# 2_10decoder.net
KiCad netlist of a schematic drawn in EAGLE
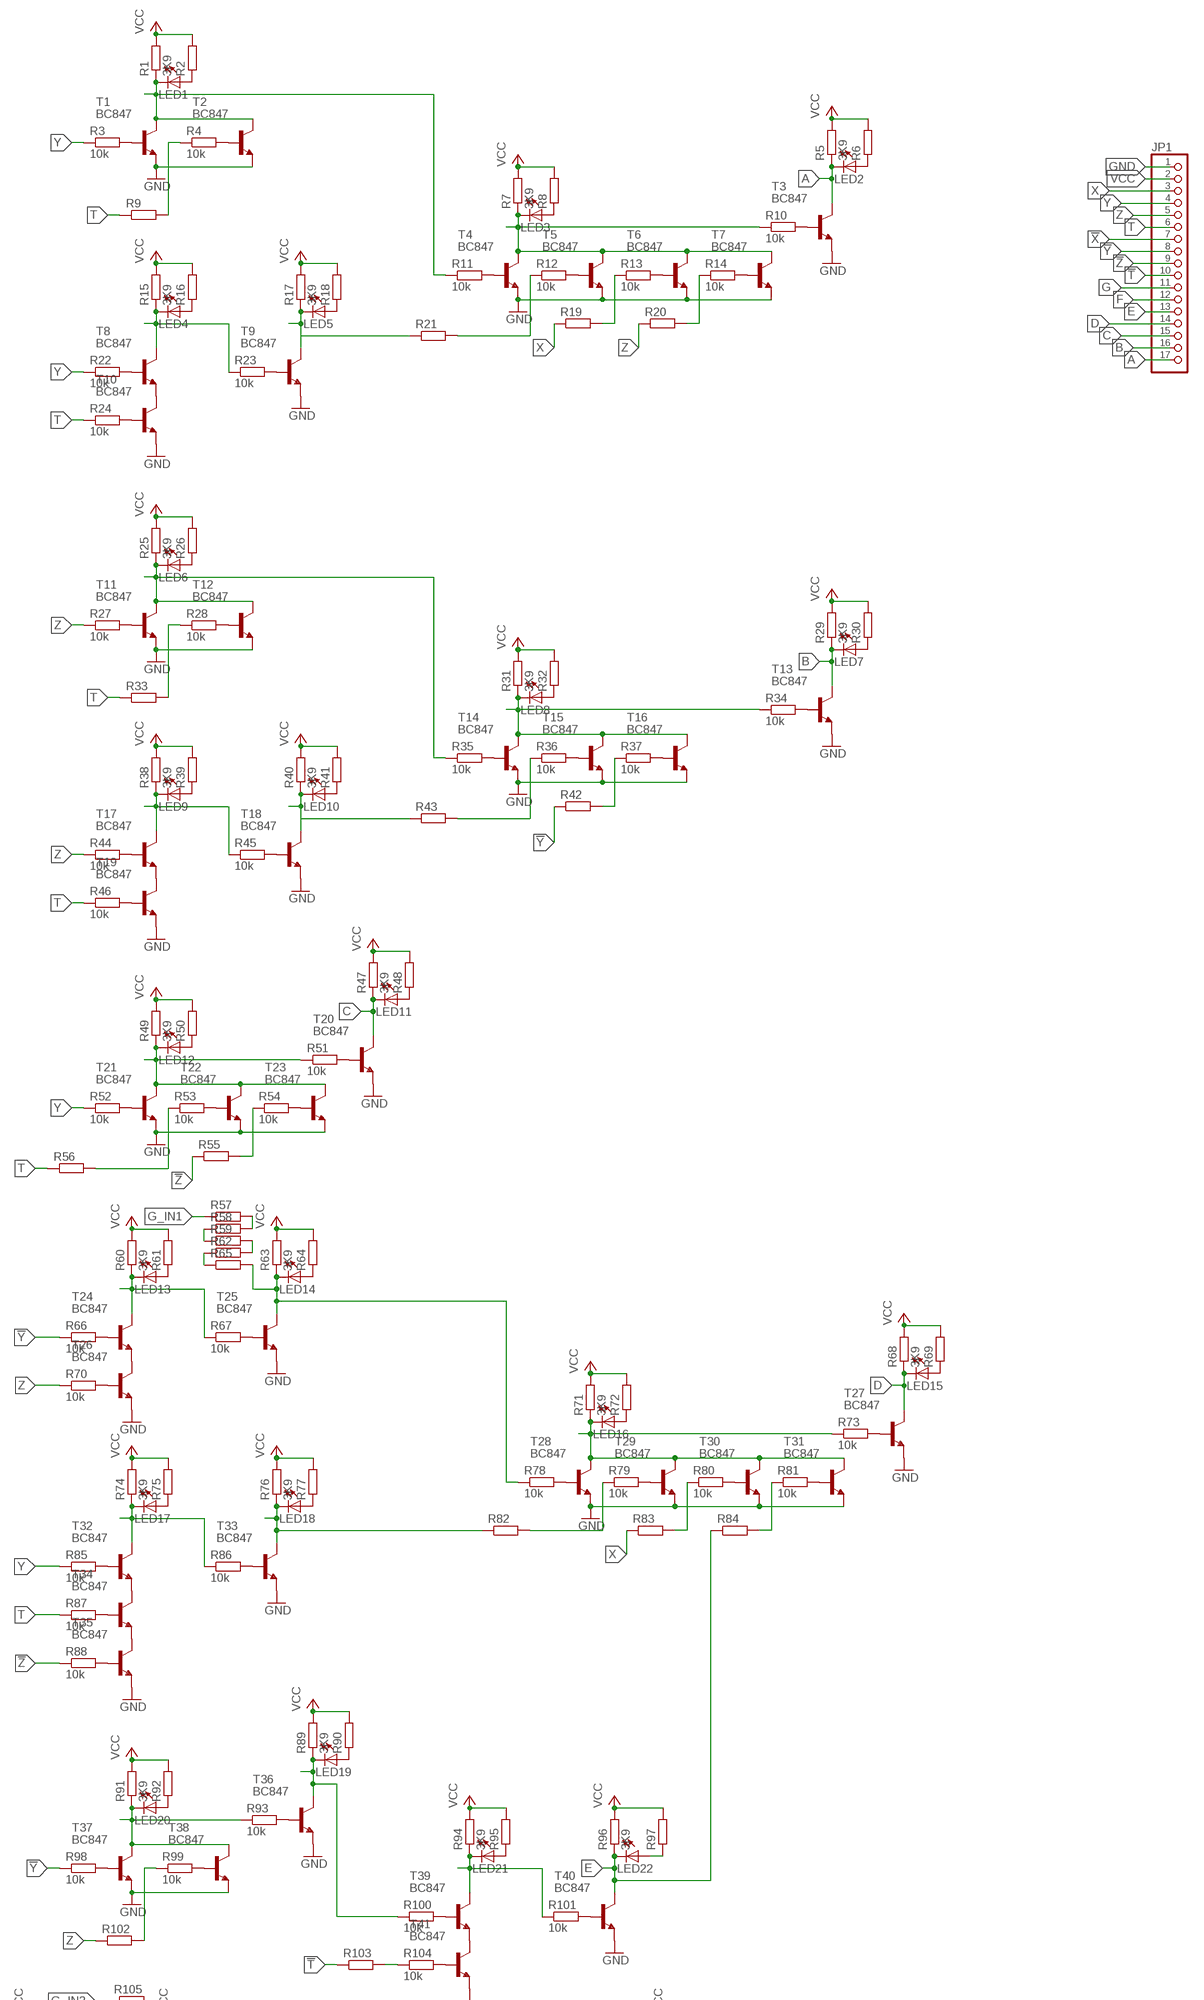
[diagram p0: schematic, sheet 1, part 1 of 2]
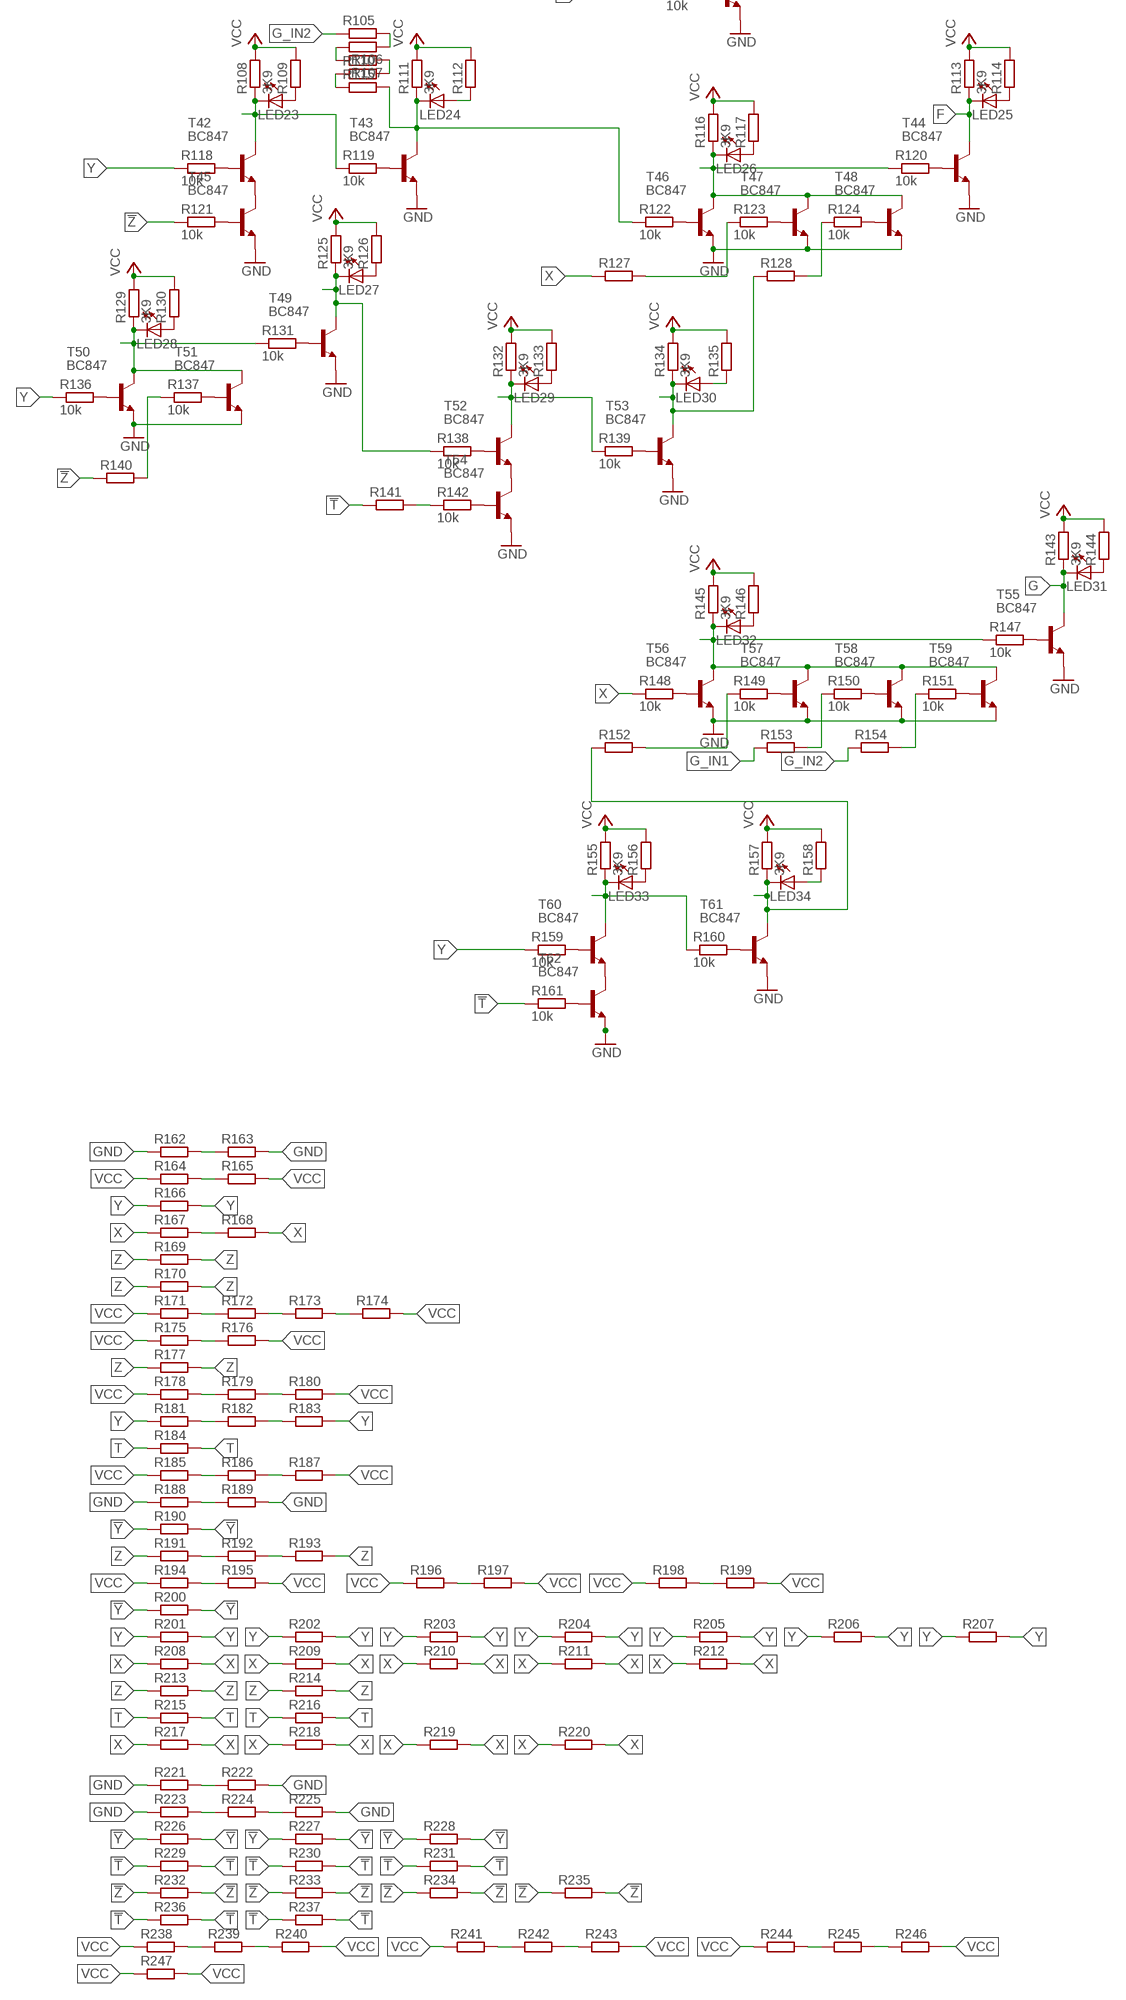
[diagram p1: schematic, sheet 1, part 2 of 2]

(export (version "E")
  (design (tool "Eeschema 10.0.6"))
  (components
    (comp (ref "JP1")
      (value "PINHD-1X17_2.54-SMD-90°")
      (footprint "eagle-import:1X17SMD_90")
      (libsource (lib "eagle-import") (part "PINHD-1X17_2.54-SMD-90°"))
    )
    (comp (ref "LED1")
      (value "LEDCHIP-LED0805")
      (footprint "eagle-import:CHIP-LED0805")
      (libsource (lib "eagle-import") (part "LEDCHIP-LED0805"))
    )
    (comp (ref "LED2")
      (value "LEDCHIP-LED0805")
      (footprint "eagle-import:CHIP-LED0805")
      (libsource (lib "eagle-import") (part "LEDCHIP-LED0805"))
    )
    (comp (ref "LED3")
      (value "LEDCHIP-LED0805")
      (footprint "eagle-import:CHIP-LED0805")
      (libsource (lib "eagle-import") (part "LEDCHIP-LED0805"))
    )
    (comp (ref "LED4")
      (value "LEDCHIP-LED0805")
      (footprint "eagle-import:CHIP-LED0805")
      (libsource (lib "eagle-import") (part "LEDCHIP-LED0805"))
    )
    (comp (ref "LED5")
      (value "LEDCHIP-LED0805")
      (footprint "eagle-import:CHIP-LED0805")
      (libsource (lib "eagle-import") (part "LEDCHIP-LED0805"))
    )
    (comp (ref "LED6")
      (value "LEDCHIP-LED0805")
      (footprint "eagle-import:CHIP-LED0805")
      (libsource (lib "eagle-import") (part "LEDCHIP-LED0805"))
    )
    (comp (ref "LED7")
      (value "LEDCHIP-LED0805")
      (footprint "eagle-import:CHIP-LED0805")
      (libsource (lib "eagle-import") (part "LEDCHIP-LED0805"))
    )
    (comp (ref "LED8")
      (value "LEDCHIP-LED0805")
      (footprint "eagle-import:CHIP-LED0805")
      (libsource (lib "eagle-import") (part "LEDCHIP-LED0805"))
    )
    (comp (ref "LED9")
      (value "LEDCHIP-LED0805")
      (footprint "eagle-import:CHIP-LED0805")
      (libsource (lib "eagle-import") (part "LEDCHIP-LED0805"))
    )
    (comp (ref "LED10")
      (value "LEDCHIP-LED0805")
      (footprint "eagle-import:CHIP-LED0805")
      (libsource (lib "eagle-import") (part "LEDCHIP-LED0805"))
    )
    (comp (ref "LED11")
      (value "LEDCHIP-LED0805")
      (footprint "eagle-import:CHIP-LED0805")
      (libsource (lib "eagle-import") (part "LEDCHIP-LED0805"))
    )
    (comp (ref "LED12")
      (value "LEDCHIP-LED0805")
      (footprint "eagle-import:CHIP-LED0805")
      (libsource (lib "eagle-import") (part "LEDCHIP-LED0805"))
    )
    (comp (ref "LED13")
      (value "LEDCHIP-LED0805")
      (footprint "eagle-import:CHIP-LED0805")
      (libsource (lib "eagle-import") (part "LEDCHIP-LED0805"))
    )
    (comp (ref "LED14")
      (value "LEDCHIP-LED0805")
      (footprint "eagle-import:CHIP-LED0805")
      (libsource (lib "eagle-import") (part "LEDCHIP-LED0805"))
    )
    (comp (ref "LED15")
      (value "LEDCHIP-LED0805")
      (footprint "eagle-import:CHIP-LED0805")
      (libsource (lib "eagle-import") (part "LEDCHIP-LED0805"))
    )
    (comp (ref "LED16")
      (value "LEDCHIP-LED0805")
      (footprint "eagle-import:CHIP-LED0805")
      (libsource (lib "eagle-import") (part "LEDCHIP-LED0805"))
    )
    (comp (ref "LED17")
      (value "LEDCHIP-LED0805")
      (footprint "eagle-import:CHIP-LED0805")
      (libsource (lib "eagle-import") (part "LEDCHIP-LED0805"))
    )
    (comp (ref "LED18")
      (value "LEDCHIP-LED0805")
      (footprint "eagle-import:CHIP-LED0805")
      (libsource (lib "eagle-import") (part "LEDCHIP-LED0805"))
    )
    (comp (ref "LED19")
      (value "LEDCHIP-LED0805")
      (footprint "eagle-import:CHIP-LED0805")
      (libsource (lib "eagle-import") (part "LEDCHIP-LED0805"))
    )
    (comp (ref "LED20")
      (value "LEDCHIP-LED0805")
      (footprint "eagle-import:CHIP-LED0805")
      (libsource (lib "eagle-import") (part "LEDCHIP-LED0805"))
    )
    (comp (ref "LED21")
      (value "LEDCHIP-LED0805")
      (footprint "eagle-import:CHIP-LED0805")
      (libsource (lib "eagle-import") (part "LEDCHIP-LED0805"))
    )
    (comp (ref "LED22")
      (value "LEDCHIP-LED0805")
      (footprint "eagle-import:CHIP-LED0805")
      (libsource (lib "eagle-import") (part "LEDCHIP-LED0805"))
    )
    (comp (ref "LED23")
      (value "LEDCHIP-LED0805")
      (footprint "eagle-import:CHIP-LED0805")
      (libsource (lib "eagle-import") (part "LEDCHIP-LED0805"))
    )
    (comp (ref "LED24")
      (value "LEDCHIP-LED0805")
      (footprint "eagle-import:CHIP-LED0805")
      (libsource (lib "eagle-import") (part "LEDCHIP-LED0805"))
    )
    (comp (ref "LED25")
      (value "LEDCHIP-LED0805")
      (footprint "eagle-import:CHIP-LED0805")
      (libsource (lib "eagle-import") (part "LEDCHIP-LED0805"))
    )
    (comp (ref "LED26")
      (value "LEDCHIP-LED0805")
      (footprint "eagle-import:CHIP-LED0805")
      (libsource (lib "eagle-import") (part "LEDCHIP-LED0805"))
    )
    (comp (ref "LED27")
      (value "LEDCHIP-LED0805")
      (footprint "eagle-import:CHIP-LED0805")
      (libsource (lib "eagle-import") (part "LEDCHIP-LED0805"))
    )
    (comp (ref "LED28")
      (value "LEDCHIP-LED0805")
      (footprint "eagle-import:CHIP-LED0805")
      (libsource (lib "eagle-import") (part "LEDCHIP-LED0805"))
    )
    (comp (ref "LED29")
      (value "LEDCHIP-LED0805")
      (footprint "eagle-import:CHIP-LED0805")
      (libsource (lib "eagle-import") (part "LEDCHIP-LED0805"))
    )
    (comp (ref "LED30")
      (value "LEDCHIP-LED0805")
      (footprint "eagle-import:CHIP-LED0805")
      (libsource (lib "eagle-import") (part "LEDCHIP-LED0805"))
    )
    (comp (ref "LED31")
      (value "LEDCHIP-LED0805")
      (footprint "eagle-import:CHIP-LED0805")
      (libsource (lib "eagle-import") (part "LEDCHIP-LED0805"))
    )
    (comp (ref "LED32")
      (value "LEDCHIP-LED0805")
      (footprint "eagle-import:CHIP-LED0805")
      (libsource (lib "eagle-import") (part "LEDCHIP-LED0805"))
    )
    (comp (ref "LED33")
      (value "LEDCHIP-LED0805")
      (footprint "eagle-import:CHIP-LED0805")
      (libsource (lib "eagle-import") (part "LEDCHIP-LED0805"))
    )
    (comp (ref "LED34")
      (value "LEDCHIP-LED0805")
      (footprint "eagle-import:CHIP-LED0805")
      (libsource (lib "eagle-import") (part "LEDCHIP-LED0805"))
    )
    (comp (ref "R1")
      (value "3K9")
      (footprint "eagle-import:M0805")
      (libsource (lib "eagle-import") (part "resistor_348_R-EU_M0805"))
    )
    (comp (ref "R2")
      (value "R-EU_M0805")
      (footprint "eagle-import:M0805")
      (libsource (lib "eagle-import") (part "resistor_348_R-EU_M0805"))
    )
    (comp (ref "R3")
      (value "10k")
      (footprint "eagle-import:M0805")
      (libsource (lib "eagle-import") (part "resistor_348_R-EU_M0805"))
    )
    (comp (ref "R4")
      (value "10k")
      (footprint "eagle-import:M0805")
      (libsource (lib "eagle-import") (part "resistor_348_R-EU_M0805"))
    )
    (comp (ref "R5")
      (value "3K9")
      (footprint "eagle-import:M0805")
      (libsource (lib "eagle-import") (part "resistor_348_R-EU_M0805"))
    )
    (comp (ref "R6")
      (value "R-EU_M0805")
      (footprint "eagle-import:M0805")
      (libsource (lib "eagle-import") (part "resistor_348_R-EU_M0805"))
    )
    (comp (ref "R7")
      (value "3K9")
      (footprint "eagle-import:M0805")
      (libsource (lib "eagle-import") (part "resistor_348_R-EU_M0805"))
    )
    (comp (ref "R8")
      (value "R-EU_M0805")
      (footprint "eagle-import:M0805")
      (libsource (lib "eagle-import") (part "resistor_348_R-EU_M0805"))
    )
    (comp (ref "R9")
      (value "R-EU_M1206")
      (footprint "eagle-import:M1206")
      (libsource (lib "eagle-import") (part "R-EU_M1206"))
    )
    (comp (ref "R10")
      (value "10k")
      (footprint "eagle-import:M0805")
      (libsource (lib "eagle-import") (part "resistor_348_R-EU_M0805"))
    )
    (comp (ref "R11")
      (value "10k")
      (footprint "eagle-import:M0805")
      (libsource (lib "eagle-import") (part "resistor_348_R-EU_M0805"))
    )
    (comp (ref "R12")
      (value "10k")
      (footprint "eagle-import:M0805")
      (libsource (lib "eagle-import") (part "resistor_348_R-EU_M0805"))
    )
    (comp (ref "R13")
      (value "10k")
      (footprint "eagle-import:M0805")
      (libsource (lib "eagle-import") (part "resistor_348_R-EU_M0805"))
    )
    (comp (ref "R14")
      (value "10k")
      (footprint "eagle-import:M0805")
      (libsource (lib "eagle-import") (part "resistor_348_R-EU_M0805"))
    )
    (comp (ref "R15")
      (value "3K9")
      (footprint "eagle-import:M0805")
      (libsource (lib "eagle-import") (part "resistor_348_R-EU_M0805"))
    )
    (comp (ref "R16")
      (value "R-EU_M0805")
      (footprint "eagle-import:M0805")
      (libsource (lib "eagle-import") (part "resistor_348_R-EU_M0805"))
    )
    (comp (ref "R17")
      (value "3K9")
      (footprint "eagle-import:M0805")
      (libsource (lib "eagle-import") (part "resistor_348_R-EU_M0805"))
    )
    (comp (ref "R18")
      (value "R-EU_M0805")
      (footprint "eagle-import:M0805")
      (libsource (lib "eagle-import") (part "resistor_348_R-EU_M0805"))
    )
    (comp (ref "R19")
      (value "R-EU_M1206")
      (footprint "eagle-import:M1206")
      (libsource (lib "eagle-import") (part "R-EU_M1206"))
    )
    (comp (ref "R20")
      (value "R-EU_M1206")
      (footprint "eagle-import:M1206")
      (libsource (lib "eagle-import") (part "R-EU_M1206"))
    )
    (comp (ref "R21")
      (value "R-EU_M1206")
      (footprint "eagle-import:M1206")
      (libsource (lib "eagle-import") (part "R-EU_M1206"))
    )
    (comp (ref "R22")
      (value "10k")
      (footprint "eagle-import:M0805")
      (libsource (lib "eagle-import") (part "resistor_348_R-EU_M0805"))
    )
    (comp (ref "R23")
      (value "10k")
      (footprint "eagle-import:M0805")
      (libsource (lib "eagle-import") (part "resistor_348_R-EU_M0805"))
    )
    (comp (ref "R24")
      (value "10k")
      (footprint "eagle-import:M0805")
      (libsource (lib "eagle-import") (part "resistor_348_R-EU_M0805"))
    )
    (comp (ref "R25")
      (value "3K9")
      (footprint "eagle-import:M0805")
      (libsource (lib "eagle-import") (part "resistor_348_R-EU_M0805"))
    )
    (comp (ref "R26")
      (value "R-EU_M0805")
      (footprint "eagle-import:M0805")
      (libsource (lib "eagle-import") (part "resistor_348_R-EU_M0805"))
    )
    (comp (ref "R27")
      (value "10k")
      (footprint "eagle-import:M0805")
      (libsource (lib "eagle-import") (part "resistor_348_R-EU_M0805"))
    )
    (comp (ref "R28")
      (value "10k")
      (footprint "eagle-import:M0805")
      (libsource (lib "eagle-import") (part "resistor_348_R-EU_M0805"))
    )
    (comp (ref "R29")
      (value "3K9")
      (footprint "eagle-import:M0805")
      (libsource (lib "eagle-import") (part "resistor_348_R-EU_M0805"))
    )
    (comp (ref "R30")
      (value "R-EU_M0805")
      (footprint "eagle-import:M0805")
      (libsource (lib "eagle-import") (part "resistor_348_R-EU_M0805"))
    )
    (comp (ref "R31")
      (value "3K9")
      (footprint "eagle-import:M0805")
      (libsource (lib "eagle-import") (part "resistor_348_R-EU_M0805"))
    )
    (comp (ref "R32")
      (value "R-EU_M0805")
      (footprint "eagle-import:M0805")
      (libsource (lib "eagle-import") (part "resistor_348_R-EU_M0805"))
    )
    (comp (ref "R33")
      (value "R-EU_M1206")
      (footprint "eagle-import:M1206")
      (libsource (lib "eagle-import") (part "R-EU_M1206"))
    )
    (comp (ref "R34")
      (value "10k")
      (footprint "eagle-import:M0805")
      (libsource (lib "eagle-import") (part "resistor_348_R-EU_M0805"))
    )
    (comp (ref "R35")
      (value "10k")
      (footprint "eagle-import:M0805")
      (libsource (lib "eagle-import") (part "resistor_348_R-EU_M0805"))
    )
    (comp (ref "R36")
      (value "10k")
      (footprint "eagle-import:M0805")
      (libsource (lib "eagle-import") (part "resistor_348_R-EU_M0805"))
    )
    (comp (ref "R37")
      (value "10k")
      (footprint "eagle-import:M0805")
      (libsource (lib "eagle-import") (part "resistor_348_R-EU_M0805"))
    )
    (comp (ref "R38")
      (value "3K9")
      (footprint "eagle-import:M0805")
      (libsource (lib "eagle-import") (part "resistor_348_R-EU_M0805"))
    )
    (comp (ref "R39")
      (value "R-EU_M0805")
      (footprint "eagle-import:M0805")
      (libsource (lib "eagle-import") (part "resistor_348_R-EU_M0805"))
    )
    (comp (ref "R40")
      (value "3K9")
      (footprint "eagle-import:M0805")
      (libsource (lib "eagle-import") (part "resistor_348_R-EU_M0805"))
    )
    (comp (ref "R41")
      (value "R-EU_M0805")
      (footprint "eagle-import:M0805")
      (libsource (lib "eagle-import") (part "resistor_348_R-EU_M0805"))
    )
    (comp (ref "R42")
      (value "R-EU_M1206")
      (footprint "eagle-import:M1206")
      (libsource (lib "eagle-import") (part "R-EU_M1206"))
    )
    (comp (ref "R43")
      (value "R-EU_M1206")
      (footprint "eagle-import:M1206")
      (libsource (lib "eagle-import") (part "R-EU_M1206"))
    )
    (comp (ref "R44")
      (value "10k")
      (footprint "eagle-import:M0805")
      (libsource (lib "eagle-import") (part "resistor_348_R-EU_M0805"))
    )
    (comp (ref "R45")
      (value "10k")
      (footprint "eagle-import:M0805")
      (libsource (lib "eagle-import") (part "resistor_348_R-EU_M0805"))
    )
    (comp (ref "R46")
      (value "10k")
      (footprint "eagle-import:M0805")
      (libsource (lib "eagle-import") (part "resistor_348_R-EU_M0805"))
    )
    (comp (ref "R47")
      (value "3K9")
      (footprint "eagle-import:M0805")
      (libsource (lib "eagle-import") (part "resistor_348_R-EU_M0805"))
    )
    (comp (ref "R48")
      (value "R-EU_M0805")
      (footprint "eagle-import:M0805")
      (libsource (lib "eagle-import") (part "resistor_348_R-EU_M0805"))
    )
    (comp (ref "R49")
      (value "3K9")
      (footprint "eagle-import:M0805")
      (libsource (lib "eagle-import") (part "resistor_348_R-EU_M0805"))
    )
    (comp (ref "R50")
      (value "R-EU_M0805")
      (footprint "eagle-import:M0805")
      (libsource (lib "eagle-import") (part "resistor_348_R-EU_M0805"))
    )
    (comp (ref "R51")
      (value "10k")
      (footprint "eagle-import:M0805")
      (libsource (lib "eagle-import") (part "resistor_348_R-EU_M0805"))
    )
    (comp (ref "R52")
      (value "10k")
      (footprint "eagle-import:M0805")
      (libsource (lib "eagle-import") (part "resistor_348_R-EU_M0805"))
    )
    (comp (ref "R53")
      (value "10k")
      (footprint "eagle-import:M0805")
      (libsource (lib "eagle-import") (part "resistor_348_R-EU_M0805"))
    )
    (comp (ref "R54")
      (value "10k")
      (footprint "eagle-import:M0805")
      (libsource (lib "eagle-import") (part "resistor_348_R-EU_M0805"))
    )
    (comp (ref "R55")
      (value "R-EU_M1206")
      (footprint "eagle-import:M1206")
      (libsource (lib "eagle-import") (part "R-EU_M1206"))
    )
    (comp (ref "R56")
      (value "R-EU_M1206")
      (footprint "eagle-import:M1206")
      (libsource (lib "eagle-import") (part "R-EU_M1206"))
    )
    (comp (ref "R57")
      (value "R-EU_M1206")
      (footprint "eagle-import:M1206")
      (libsource (lib "eagle-import") (part "R-EU_M1206"))
    )
    (comp (ref "R58")
      (value "R-EU_M1206")
      (footprint "eagle-import:M1206")
      (libsource (lib "eagle-import") (part "R-EU_M1206"))
    )
    (comp (ref "R59")
      (value "R-EU_M1206")
      (footprint "eagle-import:M1206")
      (libsource (lib "eagle-import") (part "R-EU_M1206"))
    )
    (comp (ref "R60")
      (value "3K9")
      (footprint "eagle-import:M0805")
      (libsource (lib "eagle-import") (part "resistor_348_R-EU_M0805"))
    )
    (comp (ref "R61")
      (value "R-EU_M0805")
      (footprint "eagle-import:M0805")
      (libsource (lib "eagle-import") (part "resistor_348_R-EU_M0805"))
    )
    (comp (ref "R62")
      (value "R-EU_M1206")
      (footprint "eagle-import:M1206")
      (libsource (lib "eagle-import") (part "R-EU_M1206"))
    )
    (comp (ref "R63")
      (value "3K9")
      (footprint "eagle-import:M0805")
      (libsource (lib "eagle-import") (part "resistor_348_R-EU_M0805"))
    )
    (comp (ref "R64")
      (value "R-EU_M0805")
      (footprint "eagle-import:M0805")
      (libsource (lib "eagle-import") (part "resistor_348_R-EU_M0805"))
    )
    (comp (ref "R65")
      (value "R-EU_M1206")
      (footprint "eagle-import:M1206")
      (libsource (lib "eagle-import") (part "R-EU_M1206"))
    )
    (comp (ref "R66")
      (value "10k")
      (footprint "eagle-import:M0805")
      (libsource (lib "eagle-import") (part "resistor_348_R-EU_M0805"))
    )
    (comp (ref "R67")
      (value "10k")
      (footprint "eagle-import:M0805")
      (libsource (lib "eagle-import") (part "resistor_348_R-EU_M0805"))
    )
    (comp (ref "R68")
      (value "3K9")
      (footprint "eagle-import:M0805")
      (libsource (lib "eagle-import") (part "resistor_348_R-EU_M0805"))
    )
    (comp (ref "R69")
      (value "R-EU_M0805")
      (footprint "eagle-import:M0805")
      (libsource (lib "eagle-import") (part "resistor_348_R-EU_M0805"))
    )
    (comp (ref "R70")
      (value "10k")
      (footprint "eagle-import:M0805")
      (libsource (lib "eagle-import") (part "resistor_348_R-EU_M0805"))
    )
    (comp (ref "R71")
      (value "3K9")
      (footprint "eagle-import:M0805")
      (libsource (lib "eagle-import") (part "resistor_348_R-EU_M0805"))
    )
    (comp (ref "R72")
      (value "R-EU_M0805")
      (footprint "eagle-import:M0805")
      (libsource (lib "eagle-import") (part "resistor_348_R-EU_M0805"))
    )
    (comp (ref "R73")
      (value "10k")
      (footprint "eagle-import:M0805")
      (libsource (lib "eagle-import") (part "resistor_348_R-EU_M0805"))
    )
    (comp (ref "R74")
      (value "3K9")
      (footprint "eagle-import:M0805")
      (libsource (lib "eagle-import") (part "resistor_348_R-EU_M0805"))
    )
    (comp (ref "R75")
      (value "R-EU_M0805")
      (footprint "eagle-import:M0805")
      (libsource (lib "eagle-import") (part "resistor_348_R-EU_M0805"))
    )
    (comp (ref "R76")
      (value "3K9")
      (footprint "eagle-import:M0805")
      (libsource (lib "eagle-import") (part "resistor_348_R-EU_M0805"))
    )
    (comp (ref "R77")
      (value "R-EU_M0805")
      (footprint "eagle-import:M0805")
      (libsource (lib "eagle-import") (part "resistor_348_R-EU_M0805"))
    )
    (comp (ref "R78")
      (value "10k")
      (footprint "eagle-import:M0805")
      (libsource (lib "eagle-import") (part "resistor_348_R-EU_M0805"))
    )
    (comp (ref "R79")
      (value "10k")
      (footprint "eagle-import:M0805")
      (libsource (lib "eagle-import") (part "resistor_348_R-EU_M0805"))
    )
    (comp (ref "R80")
      (value "10k")
      (footprint "eagle-import:M0805")
      (libsource (lib "eagle-import") (part "resistor_348_R-EU_M0805"))
    )
    (comp (ref "R81")
      (value "10k")
      (footprint "eagle-import:M0805")
      (libsource (lib "eagle-import") (part "resistor_348_R-EU_M0805"))
    )
    (comp (ref "R82")
      (value "R-EU_M1206")
      (footprint "eagle-import:M1206")
      (libsource (lib "eagle-import") (part "R-EU_M1206"))
    )
    (comp (ref "R83")
      (value "R-EU_M1206")
      (footprint "eagle-import:M1206")
      (libsource (lib "eagle-import") (part "R-EU_M1206"))
    )
    (comp (ref "R84")
      (value "R-EU_M1206")
      (footprint "eagle-import:M1206")
      (libsource (lib "eagle-import") (part "R-EU_M1206"))
    )
    (comp (ref "R85")
      (value "10k")
      (footprint "eagle-import:M0805")
      (libsource (lib "eagle-import") (part "resistor_348_R-EU_M0805"))
    )
    (comp (ref "R86")
      (value "10k")
      (footprint "eagle-import:M0805")
      (libsource (lib "eagle-import") (part "resistor_348_R-EU_M0805"))
    )
    (comp (ref "R87")
      (value "10k")
      (footprint "eagle-import:M0805")
      (libsource (lib "eagle-import") (part "resistor_348_R-EU_M0805"))
    )
    (comp (ref "R88")
      (value "10k")
      (footprint "eagle-import:M0805")
      (libsource (lib "eagle-import") (part "resistor_348_R-EU_M0805"))
    )
    (comp (ref "R89")
      (value "3K9")
      (footprint "eagle-import:M0805")
      (libsource (lib "eagle-import") (part "resistor_348_R-EU_M0805"))
    )
    (comp (ref "R90")
      (value "R-EU_M0805")
      (footprint "eagle-import:M0805")
      (libsource (lib "eagle-import") (part "resistor_348_R-EU_M0805"))
    )
    (comp (ref "R91")
      (value "3K9")
      (footprint "eagle-import:M0805")
      (libsource (lib "eagle-import") (part "resistor_348_R-EU_M0805"))
    )
    (comp (ref "R92")
      (value "R-EU_M0805")
      (footprint "eagle-import:M0805")
      (libsource (lib "eagle-import") (part "resistor_348_R-EU_M0805"))
    )
    (comp (ref "R93")
      (value "10k")
      (footprint "eagle-import:M0805")
      (libsource (lib "eagle-import") (part "resistor_348_R-EU_M0805"))
    )
    (comp (ref "R94")
      (value "3K9")
      (footprint "eagle-import:M0805")
      (libsource (lib "eagle-import") (part "resistor_348_R-EU_M0805"))
    )
    (comp (ref "R95")
      (value "R-EU_M0805")
      (footprint "eagle-import:M0805")
      (libsource (lib "eagle-import") (part "resistor_348_R-EU_M0805"))
    )
    (comp (ref "R96")
      (value "3K9")
      (footprint "eagle-import:M0805")
      (libsource (lib "eagle-import") (part "resistor_348_R-EU_M0805"))
    )
    (comp (ref "R97")
      (value "R-EU_M0805")
      (footprint "eagle-import:M0805")
      (libsource (lib "eagle-import") (part "resistor_348_R-EU_M0805"))
    )
    (comp (ref "R98")
      (value "10k")
      (footprint "eagle-import:M0805")
      (libsource (lib "eagle-import") (part "resistor_348_R-EU_M0805"))
    )
    (comp (ref "R99")
      (value "10k")
      (footprint "eagle-import:M0805")
      (libsource (lib "eagle-import") (part "resistor_348_R-EU_M0805"))
    )
    (comp (ref "R100")
      (value "10k")
      (footprint "eagle-import:M0805")
      (libsource (lib "eagle-import") (part "resistor_348_R-EU_M0805"))
    )
    (comp (ref "R101")
      (value "10k")
      (footprint "eagle-import:M0805")
      (libsource (lib "eagle-import") (part "resistor_348_R-EU_M0805"))
    )
    (comp (ref "R102")
      (value "R-EU_M1206")
      (footprint "eagle-import:M1206")
      (libsource (lib "eagle-import") (part "R-EU_M1206"))
    )
    (comp (ref "R103")
      (value "R-EU_M1206")
      (footprint "eagle-import:M1206")
      (libsource (lib "eagle-import") (part "R-EU_M1206"))
    )
    (comp (ref "R104")
      (value "10k")
      (footprint "eagle-import:M0805")
      (libsource (lib "eagle-import") (part "resistor_348_R-EU_M0805"))
    )
    (comp (ref "R105")
      (value "R-EU_M1206")
      (footprint "eagle-import:M1206")
      (libsource (lib "eagle-import") (part "R-EU_M1206"))
    )
    (comp (ref "R106")
      (value "R-EU_M1206")
      (footprint "eagle-import:M1206")
      (libsource (lib "eagle-import") (part "R-EU_M1206"))
    )
    (comp (ref "R107")
      (value "R-EU_M1206")
      (footprint "eagle-import:M1206")
      (libsource (lib "eagle-import") (part "R-EU_M1206"))
    )
    (comp (ref "R108")
      (value "3K9")
      (footprint "eagle-import:M0805")
      (libsource (lib "eagle-import") (part "resistor_348_R-EU_M0805"))
    )
    (comp (ref "R109")
      (value "R-EU_M0805")
      (footprint "eagle-import:M0805")
      (libsource (lib "eagle-import") (part "resistor_348_R-EU_M0805"))
    )
    (comp (ref "R110")
      (value "R-EU_M1206")
      (footprint "eagle-import:M1206")
      (libsource (lib "eagle-import") (part "R-EU_M1206"))
    )
    (comp (ref "R111")
      (value "3K9")
      (footprint "eagle-import:M0805")
      (libsource (lib "eagle-import") (part "resistor_348_R-EU_M0805"))
    )
    (comp (ref "R112")
      (value "R-EU_M0805")
      (footprint "eagle-import:M0805")
      (libsource (lib "eagle-import") (part "resistor_348_R-EU_M0805"))
    )
    (comp (ref "R113")
      (value "3K9")
      (footprint "eagle-import:M0805")
      (libsource (lib "eagle-import") (part "resistor_348_R-EU_M0805"))
    )
    (comp (ref "R114")
      (value "R-EU_M0805")
      (footprint "eagle-import:M0805")
      (libsource (lib "eagle-import") (part "resistor_348_R-EU_M0805"))
    )
    (comp (ref "R115")
      (value "R-EU_M1206")
      (footprint "eagle-import:M1206")
      (libsource (lib "eagle-import") (part "R-EU_M1206"))
    )
    (comp (ref "R116")
      (value "3K9")
      (footprint "eagle-import:M0805")
      (libsource (lib "eagle-import") (part "resistor_348_R-EU_M0805"))
    )
    (comp (ref "R117")
      (value "R-EU_M0805")
      (footprint "eagle-import:M0805")
      (libsource (lib "eagle-import") (part "resistor_348_R-EU_M0805"))
    )
    (comp (ref "R118")
      (value "10k")
      (footprint "eagle-import:M0805")
      (libsource (lib "eagle-import") (part "resistor_348_R-EU_M0805"))
    )
    (comp (ref "R119")
      (value "10k")
      (footprint "eagle-import:M0805")
      (libsource (lib "eagle-import") (part "resistor_348_R-EU_M0805"))
    )
    (comp (ref "R120")
      (value "10k")
      (footprint "eagle-import:M0805")
      (libsource (lib "eagle-import") (part "resistor_348_R-EU_M0805"))
    )
    (comp (ref "R121")
      (value "10k")
      (footprint "eagle-import:M0805")
      (libsource (lib "eagle-import") (part "resistor_348_R-EU_M0805"))
    )
    (comp (ref "R122")
      (value "10k")
      (footprint "eagle-import:M0805")
      (libsource (lib "eagle-import") (part "resistor_348_R-EU_M0805"))
    )
    (comp (ref "R123")
      (value "10k")
      (footprint "eagle-import:M0805")
      (libsource (lib "eagle-import") (part "resistor_348_R-EU_M0805"))
    )
    (comp (ref "R124")
      (value "10k")
      (footprint "eagle-import:M0805")
      (libsource (lib "eagle-import") (part "resistor_348_R-EU_M0805"))
    )
    (comp (ref "R125")
      (value "3K9")
      (footprint "eagle-import:M0805")
      (libsource (lib "eagle-import") (part "resistor_348_R-EU_M0805"))
    )
    (comp (ref "R126")
      (value "R-EU_M0805")
      (footprint "eagle-import:M0805")
      (libsource (lib "eagle-import") (part "resistor_348_R-EU_M0805"))
    )
    (comp (ref "R127")
      (value "R-EU_M1206")
      (footprint "eagle-import:M1206")
      (libsource (lib "eagle-import") (part "R-EU_M1206"))
    )
    (comp (ref "R128")
      (value "R-EU_M1206")
      (footprint "eagle-import:M1206")
      (libsource (lib "eagle-import") (part "R-EU_M1206"))
    )
    (comp (ref "R129")
      (value "3K9")
      (footprint "eagle-import:M0805")
      (libsource (lib "eagle-import") (part "resistor_348_R-EU_M0805"))
    )
    (comp (ref "R130")
      (value "R-EU_M0805")
      (footprint "eagle-import:M0805")
      (libsource (lib "eagle-import") (part "resistor_348_R-EU_M0805"))
    )
    (comp (ref "R131")
      (value "10k")
      (footprint "eagle-import:M0805")
      (libsource (lib "eagle-import") (part "resistor_348_R-EU_M0805"))
    )
    (comp (ref "R132")
      (value "3K9")
      (footprint "eagle-import:M0805")
      (libsource (lib "eagle-import") (part "resistor_348_R-EU_M0805"))
    )
    (comp (ref "R133")
      (value "R-EU_M0805")
      (footprint "eagle-import:M0805")
      (libsource (lib "eagle-import") (part "resistor_348_R-EU_M0805"))
    )
    (comp (ref "R134")
      (value "3K9")
      (footprint "eagle-import:M0805")
      (libsource (lib "eagle-import") (part "resistor_348_R-EU_M0805"))
    )
    (comp (ref "R135")
      (value "R-EU_M0805")
      (footprint "eagle-import:M0805")
      (libsource (lib "eagle-import") (part "resistor_348_R-EU_M0805"))
    )
    (comp (ref "R136")
      (value "10k")
      (footprint "eagle-import:M0805")
      (libsource (lib "eagle-import") (part "resistor_348_R-EU_M0805"))
    )
    (comp (ref "R137")
      (value "10k")
      (footprint "eagle-import:M0805")
      (libsource (lib "eagle-import") (part "resistor_348_R-EU_M0805"))
    )
    (comp (ref "R138")
      (value "10k")
      (footprint "eagle-import:M0805")
      (libsource (lib "eagle-import") (part "resistor_348_R-EU_M0805"))
    )
    (comp (ref "R139")
      (value "10k")
      (footprint "eagle-import:M0805")
      (libsource (lib "eagle-import") (part "resistor_348_R-EU_M0805"))
    )
    (comp (ref "R140")
      (value "R-EU_M1206")
      (footprint "eagle-import:M1206")
      (libsource (lib "eagle-import") (part "R-EU_M1206"))
    )
    (comp (ref "R141")
      (value "R-EU_M1206")
      (footprint "eagle-import:M1206")
      (libsource (lib "eagle-import") (part "R-EU_M1206"))
    )
    (comp (ref "R142")
      (value "10k")
      (footprint "eagle-import:M0805")
      (libsource (lib "eagle-import") (part "resistor_348_R-EU_M0805"))
    )
    (comp (ref "R143")
      (value "3K9")
      (footprint "eagle-import:M0805")
      (libsource (lib "eagle-import") (part "resistor_348_R-EU_M0805"))
    )
    (comp (ref "R144")
      (value "R-EU_M0805")
      (footprint "eagle-import:M0805")
      (libsource (lib "eagle-import") (part "resistor_348_R-EU_M0805"))
    )
    (comp (ref "R145")
      (value "3K9")
      (footprint "eagle-import:M0805")
      (libsource (lib "eagle-import") (part "resistor_348_R-EU_M0805"))
    )
    (comp (ref "R146")
      (value "R-EU_M0805")
      (footprint "eagle-import:M0805")
      (libsource (lib "eagle-import") (part "resistor_348_R-EU_M0805"))
    )
    (comp (ref "R147")
      (value "10k")
      (footprint "eagle-import:M0805")
      (libsource (lib "eagle-import") (part "resistor_348_R-EU_M0805"))
    )
    (comp (ref "R148")
      (value "10k")
      (footprint "eagle-import:M0805")
      (libsource (lib "eagle-import") (part "resistor_348_R-EU_M0805"))
    )
    (comp (ref "R149")
      (value "10k")
      (footprint "eagle-import:M0805")
      (libsource (lib "eagle-import") (part "resistor_348_R-EU_M0805"))
    )
    (comp (ref "R150")
      (value "10k")
      (footprint "eagle-import:M0805")
      (libsource (lib "eagle-import") (part "resistor_348_R-EU_M0805"))
    )
    (comp (ref "R151")
      (value "10k")
      (footprint "eagle-import:M0805")
      (libsource (lib "eagle-import") (part "resistor_348_R-EU_M0805"))
    )
    (comp (ref "R152")
      (value "R-EU_M1206")
      (footprint "eagle-import:M1206")
      (libsource (lib "eagle-import") (part "R-EU_M1206"))
    )
    (comp (ref "R153")
      (value "R-EU_M1206")
      (footprint "eagle-import:M1206")
      (libsource (lib "eagle-import") (part "R-EU_M1206"))
    )
    (comp (ref "R154")
      (value "R-EU_M1206")
      (footprint "eagle-import:M1206")
      (libsource (lib "eagle-import") (part "R-EU_M1206"))
    )
    (comp (ref "R155")
      (value "3K9")
      (footprint "eagle-import:M0805")
      (libsource (lib "eagle-import") (part "resistor_348_R-EU_M0805"))
    )
    (comp (ref "R156")
      (value "R-EU_M0805")
      (footprint "eagle-import:M0805")
      (libsource (lib "eagle-import") (part "resistor_348_R-EU_M0805"))
    )
    (comp (ref "R157")
      (value "3K9")
      (footprint "eagle-import:M0805")
      (libsource (lib "eagle-import") (part "resistor_348_R-EU_M0805"))
    )
    (comp (ref "R158")
      (value "R-EU_M0805")
      (footprint "eagle-import:M0805")
      (libsource (lib "eagle-import") (part "resistor_348_R-EU_M0805"))
    )
    (comp (ref "R159")
      (value "10k")
      (footprint "eagle-import:M0805")
      (libsource (lib "eagle-import") (part "resistor_348_R-EU_M0805"))
    )
    (comp (ref "R160")
      (value "10k")
      (footprint "eagle-import:M0805")
      (libsource (lib "eagle-import") (part "resistor_348_R-EU_M0805"))
    )
    (comp (ref "R161")
      (value "10k")
      (footprint "eagle-import:M0805")
      (libsource (lib "eagle-import") (part "resistor_348_R-EU_M0805"))
    )
    (comp (ref "R162")
      (value "R-EU_M1206")
      (footprint "eagle-import:M1206")
      (libsource (lib "eagle-import") (part "R-EU_M1206"))
    )
    (comp (ref "R163")
      (value "R-EU_M1206")
      (footprint "eagle-import:M1206")
      (libsource (lib "eagle-import") (part "R-EU_M1206"))
    )
    (comp (ref "R164")
      (value "R-EU_M1206")
      (footprint "eagle-import:M1206")
      (libsource (lib "eagle-import") (part "R-EU_M1206"))
    )
    (comp (ref "R165")
      (value "R-EU_M1206")
      (footprint "eagle-import:M1206")
      (libsource (lib "eagle-import") (part "R-EU_M1206"))
    )
    (comp (ref "R166")
      (value "R-EU_M1206")
      (footprint "eagle-import:M1206")
      (libsource (lib "eagle-import") (part "R-EU_M1206"))
    )
    (comp (ref "R167")
      (value "R-EU_M1206")
      (footprint "eagle-import:M1206")
      (libsource (lib "eagle-import") (part "R-EU_M1206"))
    )
    (comp (ref "R168")
      (value "R-EU_M1206")
      (footprint "eagle-import:M1206")
      (libsource (lib "eagle-import") (part "R-EU_M1206"))
    )
    (comp (ref "R169")
      (value "R-EU_M1206")
      (footprint "eagle-import:M1206")
      (libsource (lib "eagle-import") (part "R-EU_M1206"))
    )
    (comp (ref "R170")
      (value "R-EU_M1206")
      (footprint "eagle-import:M1206")
      (libsource (lib "eagle-import") (part "R-EU_M1206"))
    )
    (comp (ref "R171")
      (value "R-EU_M1206")
      (footprint "eagle-import:M1206")
      (libsource (lib "eagle-import") (part "R-EU_M1206"))
    )
    (comp (ref "R172")
      (value "R-EU_M1206")
      (footprint "eagle-import:M1206")
      (libsource (lib "eagle-import") (part "R-EU_M1206"))
    )
    (comp (ref "R173")
      (value "R-EU_M1206")
      (footprint "eagle-import:M1206")
      (libsource (lib "eagle-import") (part "R-EU_M1206"))
    )
    (comp (ref "R174")
      (value "R-EU_M1206")
      (footprint "eagle-import:M1206")
      (libsource (lib "eagle-import") (part "R-EU_M1206"))
    )
    (comp (ref "R175")
      (value "R-EU_M1206")
      (footprint "eagle-import:M1206")
      (libsource (lib "eagle-import") (part "R-EU_M1206"))
    )
    (comp (ref "R176")
      (value "R-EU_M1206")
      (footprint "eagle-import:M1206")
      (libsource (lib "eagle-import") (part "R-EU_M1206"))
    )
    (comp (ref "R177")
      (value "R-EU_M1206")
      (footprint "eagle-import:M1206")
      (libsource (lib "eagle-import") (part "R-EU_M1206"))
    )
    (comp (ref "R178")
      (value "R-EU_M1206")
      (footprint "eagle-import:M1206")
      (libsource (lib "eagle-import") (part "R-EU_M1206"))
    )
    (comp (ref "R179")
      (value "R-EU_M1206")
      (footprint "eagle-import:M1206")
      (libsource (lib "eagle-import") (part "R-EU_M1206"))
    )
    (comp (ref "R180")
      (value "R-EU_M1206")
      (footprint "eagle-import:M1206")
      (libsource (lib "eagle-import") (part "R-EU_M1206"))
    )
    (comp (ref "R181")
      (value "R-EU_M1206")
      (footprint "eagle-import:M1206")
      (libsource (lib "eagle-import") (part "R-EU_M1206"))
    )
    (comp (ref "R182")
      (value "R-EU_M1206")
      (footprint "eagle-import:M1206")
      (libsource (lib "eagle-import") (part "R-EU_M1206"))
    )
    (comp (ref "R183")
      (value "R-EU_M1206")
      (footprint "eagle-import:M1206")
      (libsource (lib "eagle-import") (part "R-EU_M1206"))
    )
    (comp (ref "R184")
      (value "R-EU_M1206")
      (footprint "eagle-import:M1206")
      (libsource (lib "eagle-import") (part "R-EU_M1206"))
    )
    (comp (ref "R185")
      (value "R-EU_M1206")
      (footprint "eagle-import:M1206")
      (libsource (lib "eagle-import") (part "R-EU_M1206"))
    )
    (comp (ref "R186")
      (value "R-EU_M1206")
      (footprint "eagle-import:M1206")
      (libsource (lib "eagle-import") (part "R-EU_M1206"))
    )
    (comp (ref "R187")
      (value "R-EU_M1206")
      (footprint "eagle-import:M1206")
      (libsource (lib "eagle-import") (part "R-EU_M1206"))
    )
    (comp (ref "R188")
      (value "R-EU_M1206")
      (footprint "eagle-import:M1206")
      (libsource (lib "eagle-import") (part "R-EU_M1206"))
    )
    (comp (ref "R189")
      (value "R-EU_M1206")
      (footprint "eagle-import:M1206")
      (libsource (lib "eagle-import") (part "R-EU_M1206"))
    )
    (comp (ref "R190")
      (value "R-EU_M1206")
      (footprint "eagle-import:M1206")
      (libsource (lib "eagle-import") (part "R-EU_M1206"))
    )
    (comp (ref "R191")
      (value "R-EU_M1206")
      (footprint "eagle-import:M1206")
      (libsource (lib "eagle-import") (part "R-EU_M1206"))
    )
    (comp (ref "R192")
      (value "R-EU_M1206")
      (footprint "eagle-import:M1206")
      (libsource (lib "eagle-import") (part "R-EU_M1206"))
    )
    (comp (ref "R193")
      (value "R-EU_M1206")
      (footprint "eagle-import:M1206")
      (libsource (lib "eagle-import") (part "R-EU_M1206"))
    )
    (comp (ref "R194")
      (value "R-EU_M1206")
      (footprint "eagle-import:M1206")
      (libsource (lib "eagle-import") (part "R-EU_M1206"))
    )
    (comp (ref "R195")
      (value "R-EU_M1206")
      (footprint "eagle-import:M1206")
      (libsource (lib "eagle-import") (part "R-EU_M1206"))
    )
    (comp (ref "R196")
      (value "R-EU_M1206")
      (footprint "eagle-import:M1206")
      (libsource (lib "eagle-import") (part "R-EU_M1206"))
    )
    (comp (ref "R197")
      (value "R-EU_M1206")
      (footprint "eagle-import:M1206")
      (libsource (lib "eagle-import") (part "R-EU_M1206"))
    )
    (comp (ref "R198")
      (value "R-EU_M1206")
      (footprint "eagle-import:M1206")
      (libsource (lib "eagle-import") (part "R-EU_M1206"))
    )
    (comp (ref "R199")
      (value "R-EU_M1206")
      (footprint "eagle-import:M1206")
      (libsource (lib "eagle-import") (part "R-EU_M1206"))
    )
    (comp (ref "R200")
      (value "R-EU_M1206")
      (footprint "eagle-import:M1206")
      (libsource (lib "eagle-import") (part "R-EU_M1206"))
    )
    (comp (ref "R201")
      (value "R-EU_M1206")
      (footprint "eagle-import:M1206")
      (libsource (lib "eagle-import") (part "R-EU_M1206"))
    )
    (comp (ref "R202")
      (value "R-EU_M1206")
      (footprint "eagle-import:M1206")
      (libsource (lib "eagle-import") (part "R-EU_M1206"))
    )
    (comp (ref "R203")
      (value "R-EU_M1206")
      (footprint "eagle-import:M1206")
      (libsource (lib "eagle-import") (part "R-EU_M1206"))
    )
    (comp (ref "R204")
      (value "R-EU_M1206")
      (footprint "eagle-import:M1206")
      (libsource (lib "eagle-import") (part "R-EU_M1206"))
    )
    (comp (ref "R205")
      (value "R-EU_M1206")
      (footprint "eagle-import:M1206")
      (libsource (lib "eagle-import") (part "R-EU_M1206"))
    )
    (comp (ref "R206")
      (value "R-EU_M1206")
      (footprint "eagle-import:M1206")
      (libsource (lib "eagle-import") (part "R-EU_M1206"))
    )
    (comp (ref "R207")
      (value "R-EU_M1206")
      (footprint "eagle-import:M1206")
      (libsource (lib "eagle-import") (part "R-EU_M1206"))
    )
    (comp (ref "R208")
      (value "R-EU_M1206")
      (footprint "eagle-import:M1206")
      (libsource (lib "eagle-import") (part "R-EU_M1206"))
    )
    (comp (ref "R209")
      (value "R-EU_M1206")
      (footprint "eagle-import:M1206")
      (libsource (lib "eagle-import") (part "R-EU_M1206"))
    )
    (comp (ref "R210")
      (value "R-EU_M1206")
      (footprint "eagle-import:M1206")
      (libsource (lib "eagle-import") (part "R-EU_M1206"))
    )
    (comp (ref "R211")
      (value "R-EU_M1206")
      (footprint "eagle-import:M1206")
      (libsource (lib "eagle-import") (part "R-EU_M1206"))
    )
    (comp (ref "R212")
      (value "R-EU_M1206")
      (footprint "eagle-import:M1206")
      (libsource (lib "eagle-import") (part "R-EU_M1206"))
    )
    (comp (ref "R213")
      (value "R-EU_M1206")
      (footprint "eagle-import:M1206")
      (libsource (lib "eagle-import") (part "R-EU_M1206"))
    )
    (comp (ref "R214")
      (value "R-EU_M1206")
      (footprint "eagle-import:M1206")
      (libsource (lib "eagle-import") (part "R-EU_M1206"))
    )
    (comp (ref "R215")
      (value "R-EU_M1206")
      (footprint "eagle-import:M1206")
      (libsource (lib "eagle-import") (part "R-EU_M1206"))
    )
    (comp (ref "R216")
      (value "R-EU_M1206")
      (footprint "eagle-import:M1206")
      (libsource (lib "eagle-import") (part "R-EU_M1206"))
    )
    (comp (ref "R217")
      (value "R-EU_M1206")
      (footprint "eagle-import:M1206")
      (libsource (lib "eagle-import") (part "R-EU_M1206"))
    )
    (comp (ref "R218")
      (value "R-EU_M1206")
      (footprint "eagle-import:M1206")
      (libsource (lib "eagle-import") (part "R-EU_M1206"))
    )
    (comp (ref "R219")
      (value "R-EU_M1206")
      (footprint "eagle-import:M1206")
      (libsource (lib "eagle-import") (part "R-EU_M1206"))
    )
    (comp (ref "R220")
      (value "R-EU_M1206")
      (footprint "eagle-import:M1206")
      (libsource (lib "eagle-import") (part "R-EU_M1206"))
    )
    (comp (ref "R221")
      (value "R-EU_M1206")
      (footprint "eagle-import:M1206")
      (libsource (lib "eagle-import") (part "R-EU_M1206"))
    )
    (comp (ref "R222")
      (value "R-EU_M1206")
      (footprint "eagle-import:M1206")
      (libsource (lib "eagle-import") (part "R-EU_M1206"))
    )
    (comp (ref "R223")
      (value "R-EU_M1206")
      (footprint "eagle-import:M1206")
      (libsource (lib "eagle-import") (part "R-EU_M1206"))
    )
    (comp (ref "R224")
      (value "R-EU_M1206")
      (footprint "eagle-import:M1206")
      (libsource (lib "eagle-import") (part "R-EU_M1206"))
    )
    (comp (ref "R225")
      (value "R-EU_M1206")
      (footprint "eagle-import:M1206")
      (libsource (lib "eagle-import") (part "R-EU_M1206"))
    )
    (comp (ref "R226")
      (value "R-EU_M1206")
      (footprint "eagle-import:M1206")
      (libsource (lib "eagle-import") (part "R-EU_M1206"))
    )
    (comp (ref "R227")
      (value "R-EU_M1206")
      (footprint "eagle-import:M1206")
      (libsource (lib "eagle-import") (part "R-EU_M1206"))
    )
    (comp (ref "R228")
      (value "R-EU_M1206")
      (footprint "eagle-import:M1206")
      (libsource (lib "eagle-import") (part "R-EU_M1206"))
    )
    (comp (ref "R229")
      (value "R-EU_M1206")
      (footprint "eagle-import:M1206")
      (libsource (lib "eagle-import") (part "R-EU_M1206"))
    )
    (comp (ref "R230")
      (value "R-EU_M1206")
      (footprint "eagle-import:M1206")
      (libsource (lib "eagle-import") (part "R-EU_M1206"))
    )
    (comp (ref "R231")
      (value "R-EU_M1206")
      (footprint "eagle-import:M1206")
      (libsource (lib "eagle-import") (part "R-EU_M1206"))
    )
    (comp (ref "R232")
      (value "R-EU_M1206")
      (footprint "eagle-import:M1206")
      (libsource (lib "eagle-import") (part "R-EU_M1206"))
    )
    (comp (ref "R233")
      (value "R-EU_M1206")
      (footprint "eagle-import:M1206")
      (libsource (lib "eagle-import") (part "R-EU_M1206"))
    )
    (comp (ref "R234")
      (value "R-EU_M1206")
      (footprint "eagle-import:M1206")
      (libsource (lib "eagle-import") (part "R-EU_M1206"))
    )
    (comp (ref "R235")
      (value "R-EU_M1206")
      (footprint "eagle-import:M1206")
      (libsource (lib "eagle-import") (part "R-EU_M1206"))
    )
    (comp (ref "R236")
      (value "R-EU_M1206")
      (footprint "eagle-import:M1206")
      (libsource (lib "eagle-import") (part "R-EU_M1206"))
    )
    (comp (ref "R237")
      (value "R-EU_M1206")
      (footprint "eagle-import:M1206")
      (libsource (lib "eagle-import") (part "R-EU_M1206"))
    )
    (comp (ref "R238")
      (value "R-EU_M1206")
      (footprint "eagle-import:M1206")
      (libsource (lib "eagle-import") (part "R-EU_M1206"))
    )
    (comp (ref "R239")
      (value "R-EU_M1206")
      (footprint "eagle-import:M1206")
      (libsource (lib "eagle-import") (part "R-EU_M1206"))
    )
    (comp (ref "R240")
      (value "R-EU_M1206")
      (footprint "eagle-import:M1206")
      (libsource (lib "eagle-import") (part "R-EU_M1206"))
    )
    (comp (ref "R241")
      (value "R-EU_M1206")
      (footprint "eagle-import:M1206")
      (libsource (lib "eagle-import") (part "R-EU_M1206"))
    )
    (comp (ref "R242")
      (value "R-EU_M1206")
      (footprint "eagle-import:M1206")
      (libsource (lib "eagle-import") (part "R-EU_M1206"))
    )
    (comp (ref "R243")
      (value "R-EU_M1206")
      (footprint "eagle-import:M1206")
      (libsource (lib "eagle-import") (part "R-EU_M1206"))
    )
    (comp (ref "R244")
      (value "R-EU_M1206")
      (footprint "eagle-import:M1206")
      (libsource (lib "eagle-import") (part "R-EU_M1206"))
    )
    (comp (ref "R245")
      (value "R-EU_M1206")
      (footprint "eagle-import:M1206")
      (libsource (lib "eagle-import") (part "R-EU_M1206"))
    )
    (comp (ref "R246")
      (value "R-EU_M1206")
      (footprint "eagle-import:M1206")
      (libsource (lib "eagle-import") (part "R-EU_M1206"))
    )
    (comp (ref "R247")
      (value "R-EU_M1206")
      (footprint "eagle-import:M1206")
      (libsource (lib "eagle-import") (part "R-EU_M1206"))
    )
    (comp (ref "T1")
      (value "BC847")
      (footprint "eagle-import:SOT23")
      (libsource (lib "eagle-import") (part "BC847"))
    )
    (comp (ref "T2")
      (value "BC847")
      (footprint "eagle-import:SOT23")
      (libsource (lib "eagle-import") (part "BC847"))
    )
    (comp (ref "T3")
      (value "BC847")
      (footprint "eagle-import:SOT23")
      (libsource (lib "eagle-import") (part "BC847"))
    )
    (comp (ref "T4")
      (value "BC847")
      (footprint "eagle-import:SOT23")
      (libsource (lib "eagle-import") (part "BC847"))
    )
    (comp (ref "T5")
      (value "BC847")
      (footprint "eagle-import:SOT23")
      (libsource (lib "eagle-import") (part "BC847"))
    )
    (comp (ref "T6")
      (value "BC847")
      (footprint "eagle-import:SOT23")
      (libsource (lib "eagle-import") (part "BC847"))
    )
    (comp (ref "T7")
      (value "BC847")
      (footprint "eagle-import:SOT23")
      (libsource (lib "eagle-import") (part "BC847"))
    )
    (comp (ref "T8")
      (value "BC847")
      (footprint "eagle-import:SOT23")
      (libsource (lib "eagle-import") (part "BC847"))
    )
    (comp (ref "T9")
      (value "BC847")
      (footprint "eagle-import:SOT23")
      (libsource (lib "eagle-import") (part "BC847"))
    )
    (comp (ref "T10")
      (value "BC847")
      (footprint "eagle-import:SOT23")
      (libsource (lib "eagle-import") (part "BC847"))
    )
    (comp (ref "T11")
      (value "BC847")
      (footprint "eagle-import:SOT23")
      (libsource (lib "eagle-import") (part "BC847"))
    )
    (comp (ref "T12")
      (value "BC847")
      (footprint "eagle-import:SOT23")
      (libsource (lib "eagle-import") (part "BC847"))
    )
    (comp (ref "T13")
      (value "BC847")
      (footprint "eagle-import:SOT23")
      (libsource (lib "eagle-import") (part "BC847"))
    )
    (comp (ref "T14")
      (value "BC847")
      (footprint "eagle-import:SOT23")
      (libsource (lib "eagle-import") (part "BC847"))
    )
    (comp (ref "T15")
      (value "BC847")
      (footprint "eagle-import:SOT23")
      (libsource (lib "eagle-import") (part "BC847"))
    )
    (comp (ref "T16")
      (value "BC847")
      (footprint "eagle-import:SOT23")
      (libsource (lib "eagle-import") (part "BC847"))
    )
    (comp (ref "T17")
      (value "BC847")
      (footprint "eagle-import:SOT23")
      (libsource (lib "eagle-import") (part "BC847"))
    )
    (comp (ref "T18")
      (value "BC847")
      (footprint "eagle-import:SOT23")
      (libsource (lib "eagle-import") (part "BC847"))
    )
    (comp (ref "T19")
      (value "BC847")
      (footprint "eagle-import:SOT23")
      (libsource (lib "eagle-import") (part "BC847"))
    )
    (comp (ref "T20")
      (value "BC847")
      (footprint "eagle-import:SOT23")
      (libsource (lib "eagle-import") (part "BC847"))
    )
    (comp (ref "T21")
      (value "BC847")
      (footprint "eagle-import:SOT23")
      (libsource (lib "eagle-import") (part "BC847"))
    )
    (comp (ref "T22")
      (value "BC847")
      (footprint "eagle-import:SOT23")
      (libsource (lib "eagle-import") (part "BC847"))
    )
    (comp (ref "T23")
      (value "BC847")
      (footprint "eagle-import:SOT23")
      (libsource (lib "eagle-import") (part "BC847"))
    )
    (comp (ref "T24")
      (value "BC847")
      (footprint "eagle-import:SOT23")
      (libsource (lib "eagle-import") (part "BC847"))
    )
    (comp (ref "T25")
      (value "BC847")
      (footprint "eagle-import:SOT23")
      (libsource (lib "eagle-import") (part "BC847"))
    )
    (comp (ref "T26")
      (value "BC847")
      (footprint "eagle-import:SOT23")
      (libsource (lib "eagle-import") (part "BC847"))
    )
    (comp (ref "T27")
      (value "BC847")
      (footprint "eagle-import:SOT23")
      (libsource (lib "eagle-import") (part "BC847"))
    )
    (comp (ref "T28")
      (value "BC847")
      (footprint "eagle-import:SOT23")
      (libsource (lib "eagle-import") (part "BC847"))
    )
    (comp (ref "T29")
      (value "BC847")
      (footprint "eagle-import:SOT23")
      (libsource (lib "eagle-import") (part "BC847"))
    )
    (comp (ref "T30")
      (value "BC847")
      (footprint "eagle-import:SOT23")
      (libsource (lib "eagle-import") (part "BC847"))
    )
    (comp (ref "T31")
      (value "BC847")
      (footprint "eagle-import:SOT23")
      (libsource (lib "eagle-import") (part "BC847"))
    )
    (comp (ref "T32")
      (value "BC847")
      (footprint "eagle-import:SOT23")
      (libsource (lib "eagle-import") (part "BC847"))
    )
    (comp (ref "T33")
      (value "BC847")
      (footprint "eagle-import:SOT23")
      (libsource (lib "eagle-import") (part "BC847"))
    )
    (comp (ref "T34")
      (value "BC847")
      (footprint "eagle-import:SOT23")
      (libsource (lib "eagle-import") (part "BC847"))
    )
    (comp (ref "T35")
      (value "BC847")
      (footprint "eagle-import:SOT23")
      (libsource (lib "eagle-import") (part "BC847"))
    )
    (comp (ref "T36")
      (value "BC847")
      (footprint "eagle-import:SOT23")
      (libsource (lib "eagle-import") (part "BC847"))
    )
    (comp (ref "T37")
      (value "BC847")
      (footprint "eagle-import:SOT23")
      (libsource (lib "eagle-import") (part "BC847"))
    )
    (comp (ref "T38")
      (value "BC847")
      (footprint "eagle-import:SOT23")
      (libsource (lib "eagle-import") (part "BC847"))
    )
    (comp (ref "T39")
      (value "BC847")
      (footprint "eagle-import:SOT23")
      (libsource (lib "eagle-import") (part "BC847"))
    )
    (comp (ref "T40")
      (value "BC847")
      (footprint "eagle-import:SOT23")
      (libsource (lib "eagle-import") (part "BC847"))
    )
    (comp (ref "T41")
      (value "BC847")
      (footprint "eagle-import:SOT23")
      (libsource (lib "eagle-import") (part "BC847"))
    )
    (comp (ref "T42")
      (value "BC847")
      (footprint "eagle-import:SOT23")
      (libsource (lib "eagle-import") (part "BC847"))
    )
    (comp (ref "T43")
      (value "BC847")
      (footprint "eagle-import:SOT23")
      (libsource (lib "eagle-import") (part "BC847"))
    )
    (comp (ref "T44")
      (value "BC847")
      (footprint "eagle-import:SOT23")
      (libsource (lib "eagle-import") (part "BC847"))
    )
    (comp (ref "T45")
      (value "BC847")
      (footprint "eagle-import:SOT23")
      (libsource (lib "eagle-import") (part "BC847"))
    )
    (comp (ref "T46")
      (value "BC847")
      (footprint "eagle-import:SOT23")
      (libsource (lib "eagle-import") (part "BC847"))
    )
    (comp (ref "T47")
      (value "BC847")
      (footprint "eagle-import:SOT23")
      (libsource (lib "eagle-import") (part "BC847"))
    )
    (comp (ref "T48")
      (value "BC847")
      (footprint "eagle-import:SOT23")
      (libsource (lib "eagle-import") (part "BC847"))
    )
    (comp (ref "T49")
      (value "BC847")
      (footprint "eagle-import:SOT23")
      (libsource (lib "eagle-import") (part "BC847"))
    )
    (comp (ref "T50")
      (value "BC847")
      (footprint "eagle-import:SOT23")
      (libsource (lib "eagle-import") (part "BC847"))
    )
    (comp (ref "T51")
      (value "BC847")
      (footprint "eagle-import:SOT23")
      (libsource (lib "eagle-import") (part "BC847"))
    )
    (comp (ref "T52")
      (value "BC847")
      (footprint "eagle-import:SOT23")
      (libsource (lib "eagle-import") (part "BC847"))
    )
    (comp (ref "T53")
      (value "BC847")
      (footprint "eagle-import:SOT23")
      (libsource (lib "eagle-import") (part "BC847"))
    )
    (comp (ref "T54")
      (value "BC847")
      (footprint "eagle-import:SOT23")
      (libsource (lib "eagle-import") (part "BC847"))
    )
    (comp (ref "T55")
      (value "BC847")
      (footprint "eagle-import:SOT23")
      (libsource (lib "eagle-import") (part "BC847"))
    )
    (comp (ref "T56")
      (value "BC847")
      (footprint "eagle-import:SOT23")
      (libsource (lib "eagle-import") (part "BC847"))
    )
    (comp (ref "T57")
      (value "BC847")
      (footprint "eagle-import:SOT23")
      (libsource (lib "eagle-import") (part "BC847"))
    )
    (comp (ref "T58")
      (value "BC847")
      (footprint "eagle-import:SOT23")
      (libsource (lib "eagle-import") (part "BC847"))
    )
    (comp (ref "T59")
      (value "BC847")
      (footprint "eagle-import:SOT23")
      (libsource (lib "eagle-import") (part "BC847"))
    )
    (comp (ref "T60")
      (value "BC847")
      (footprint "eagle-import:SOT23")
      (libsource (lib "eagle-import") (part "BC847"))
    )
    (comp (ref "T61")
      (value "BC847")
      (footprint "eagle-import:SOT23")
      (libsource (lib "eagle-import") (part "BC847"))
    )
    (comp (ref "T62")
      (value "BC847")
      (footprint "eagle-import:SOT23")
      (libsource (lib "eagle-import") (part "BC847"))
    )
  )
  (nets
    (net (code "1") (name "/~{T}") (class "Default")
      (node (ref "JP1") (pin "10") (pinfunction "10_10") (pintype "passive"))
      (node (ref "R103") (pin "1") (pinfunction "1_1") (pintype "passive"))
      (node (ref "R141") (pin "1") (pinfunction "1_1") (pintype "passive"))
      (node (ref "R161") (pin "1") (pinfunction "1_1") (pintype "passive"))
      (node (ref "R229") (pin "1") (pinfunction "1_1") (pintype "passive"))
      (node (ref "R229") (pin "2") (pinfunction "2_2") (pintype "passive"))
      (node (ref "R230") (pin "1") (pinfunction "1_1") (pintype "passive"))
      (node (ref "R230") (pin "2") (pinfunction "2_2") (pintype "passive"))
      (node (ref "R231") (pin "1") (pinfunction "1_1") (pintype "passive"))
      (node (ref "R231") (pin "2") (pinfunction "2_2") (pintype "passive"))
      (node (ref "R236") (pin "1") (pinfunction "1_1") (pintype "passive"))
      (node (ref "R236") (pin "2") (pinfunction "2_2") (pintype "passive"))
      (node (ref "R237") (pin "1") (pinfunction "1_1") (pintype "passive"))
      (node (ref "R237") (pin "2") (pinfunction "2_2") (pintype "passive"))
    )
    (net (code "2") (name "/~{X}") (class "Default")
      (node (ref "JP1") (pin "7") (pinfunction "7_7") (pintype "passive"))
    )
    (net (code "3") (name "/~{Y}") (class "Default")
      (node (ref "JP1") (pin "8") (pinfunction "8_8") (pintype "passive"))
      (node (ref "R190") (pin "1") (pinfunction "1_1") (pintype "passive"))
      (node (ref "R190") (pin "2") (pinfunction "2_2") (pintype "passive"))
      (node (ref "R200") (pin "1") (pinfunction "1_1") (pintype "passive"))
      (node (ref "R200") (pin "2") (pinfunction "2_2") (pintype "passive"))
      (node (ref "R226") (pin "1") (pinfunction "1_1") (pintype "passive"))
      (node (ref "R226") (pin "2") (pinfunction "2_2") (pintype "passive"))
      (node (ref "R227") (pin "1") (pinfunction "1_1") (pintype "passive"))
      (node (ref "R227") (pin "2") (pinfunction "2_2") (pintype "passive"))
      (node (ref "R228") (pin "1") (pinfunction "1_1") (pintype "passive"))
      (node (ref "R228") (pin "2") (pinfunction "2_2") (pintype "passive"))
      (node (ref "R42") (pin "1") (pinfunction "1_1") (pintype "passive"))
      (node (ref "R66") (pin "1") (pinfunction "1_1") (pintype "passive"))
      (node (ref "R98") (pin "1") (pinfunction "1_1") (pintype "passive"))
    )
    (net (code "4") (name "/~{Z}") (class "Default")
      (node (ref "JP1") (pin "9") (pinfunction "9_9") (pintype "passive"))
      (node (ref "R121") (pin "1") (pinfunction "1_1") (pintype "passive"))
      (node (ref "R140") (pin "1") (pinfunction "1_1") (pintype "passive"))
      (node (ref "R232") (pin "1") (pinfunction "1_1") (pintype "passive"))
      (node (ref "R232") (pin "2") (pinfunction "2_2") (pintype "passive"))
      (node (ref "R233") (pin "1") (pinfunction "1_1") (pintype "passive"))
      (node (ref "R233") (pin "2") (pinfunction "2_2") (pintype "passive"))
      (node (ref "R234") (pin "1") (pinfunction "1_1") (pintype "passive"))
      (node (ref "R234") (pin "2") (pinfunction "2_2") (pintype "passive"))
      (node (ref "R235") (pin "1") (pinfunction "1_1") (pintype "passive"))
      (node (ref "R235") (pin "2") (pinfunction "2_2") (pintype "passive"))
      (node (ref "R55") (pin "1") (pinfunction "1_1") (pintype "passive"))
      (node (ref "R88") (pin "1") (pinfunction "1_1") (pintype "passive"))
    )
    (net (code "5") (name "A") (class "Default")
      (node (ref "JP1") (pin "17") (pinfunction "17_17") (pintype "passive"))
      (node (ref "LED2") (pin "C") (pinfunction "C_C") (pintype "passive"))
      (node (ref "R5") (pin "1") (pinfunction "1_1") (pintype "passive"))
      (node (ref "T3") (pin "3") (pinfunction "C_3") (pintype "passive"))
    )
    (net (code "6") (name "B") (class "Default")
      (node (ref "JP1") (pin "16") (pinfunction "16_16") (pintype "passive"))
      (node (ref "LED7") (pin "C") (pinfunction "C_C") (pintype "passive"))
      (node (ref "R29") (pin "1") (pinfunction "1_1") (pintype "passive"))
      (node (ref "T13") (pin "3") (pinfunction "C_3") (pintype "passive"))
    )
    (net (code "7") (name "C") (class "Default")
      (node (ref "JP1") (pin "15") (pinfunction "15_15") (pintype "passive"))
      (node (ref "LED11") (pin "C") (pinfunction "C_C") (pintype "passive"))
      (node (ref "R47") (pin "1") (pinfunction "1_1") (pintype "passive"))
      (node (ref "T20") (pin "3") (pinfunction "C_3") (pintype "passive"))
    )
    (net (code "8") (name "D") (class "Default")
      (node (ref "JP1") (pin "14") (pinfunction "14_14") (pintype "passive"))
      (node (ref "LED15") (pin "C") (pinfunction "C_C") (pintype "passive"))
      (node (ref "R68") (pin "1") (pinfunction "1_1") (pintype "passive"))
      (node (ref "T27") (pin "3") (pinfunction "C_3") (pintype "passive"))
    )
    (net (code "9") (name "E") (class "Default")
      (node (ref "JP1") (pin "13") (pinfunction "13_13") (pintype "passive"))
      (node (ref "LED22") (pin "C") (pinfunction "C_C") (pintype "passive"))
      (node (ref "R84") (pin "1") (pinfunction "1_1") (pintype "passive"))
      (node (ref "R96") (pin "1") (pinfunction "1_1") (pintype "passive"))
      (node (ref "T40") (pin "3") (pinfunction "C_3") (pintype "passive"))
    )
    (net (code "10") (name "F") (class "Default")
      (node (ref "JP1") (pin "12") (pinfunction "12_12") (pintype "passive"))
      (node (ref "LED25") (pin "C") (pinfunction "C_C") (pintype "passive"))
      (node (ref "R113") (pin "1") (pinfunction "1_1") (pintype "passive"))
      (node (ref "T44") (pin "3") (pinfunction "C_3") (pintype "passive"))
    )
    (net (code "11") (name "G") (class "Default")
      (node (ref "JP1") (pin "11") (pinfunction "11_11") (pintype "passive"))
      (node (ref "LED31") (pin "C") (pinfunction "C_C") (pintype "passive"))
      (node (ref "R143") (pin "1") (pinfunction "1_1") (pintype "passive"))
      (node (ref "T55") (pin "3") (pinfunction "C_3") (pintype "passive"))
    )
    (net (code "12") (name "GND") (class "Default")
      (node (ref "JP1") (pin "1") (pinfunction "1_1") (pintype "passive"))
      (node (ref "R162") (pin "1") (pinfunction "1_1") (pintype "passive"))
      (node (ref "R163") (pin "2") (pinfunction "2_2") (pintype "passive"))
      (node (ref "R188") (pin "1") (pinfunction "1_1") (pintype "passive"))
      (node (ref "R188") (pin "2") (pinfunction "2_2") (pintype "passive"))
      (node (ref "R189") (pin "1") (pinfunction "1_1") (pintype "passive"))
      (node (ref "R189") (pin "2") (pinfunction "2_2") (pintype "passive"))
      (node (ref "R221") (pin "1") (pinfunction "1_1") (pintype "passive"))
      (node (ref "R221") (pin "2") (pinfunction "2_2") (pintype "passive"))
      (node (ref "R222") (pin "1") (pinfunction "1_1") (pintype "passive"))
      (node (ref "R222") (pin "2") (pinfunction "2_2") (pintype "passive"))
      (node (ref "R223") (pin "1") (pinfunction "1_1") (pintype "passive"))
      (node (ref "R223") (pin "2") (pinfunction "2_2") (pintype "passive"))
      (node (ref "R224") (pin "1") (pinfunction "1_1") (pintype "passive"))
      (node (ref "R224") (pin "2") (pinfunction "2_2") (pintype "passive"))
      (node (ref "R225") (pin "1") (pinfunction "1_1") (pintype "passive"))
      (node (ref "R225") (pin "2") (pinfunction "2_2") (pintype "passive"))
      (node (ref "T1") (pin "2") (pinfunction "E_2") (pintype "passive"))
      (node (ref "T10") (pin "2") (pinfunction "E_2") (pintype "passive"))
      (node (ref "T11") (pin "2") (pinfunction "E_2") (pintype "passive"))
      (node (ref "T12") (pin "2") (pinfunction "E_2") (pintype "passive"))
      (node (ref "T13") (pin "2") (pinfunction "E_2") (pintype "passive"))
      (node (ref "T14") (pin "2") (pinfunction "E_2") (pintype "passive"))
      (node (ref "T15") (pin "2") (pinfunction "E_2") (pintype "passive"))
      (node (ref "T16") (pin "2") (pinfunction "E_2") (pintype "passive"))
      (node (ref "T18") (pin "2") (pinfunction "E_2") (pintype "passive"))
      (node (ref "T19") (pin "2") (pinfunction "E_2") (pintype "passive"))
      (node (ref "T2") (pin "2") (pinfunction "E_2") (pintype "passive"))
      (node (ref "T20") (pin "2") (pinfunction "E_2") (pintype "passive"))
      (node (ref "T21") (pin "2") (pinfunction "E_2") (pintype "passive"))
      (node (ref "T22") (pin "2") (pinfunction "E_2") (pintype "passive"))
      (node (ref "T23") (pin "2") (pinfunction "E_2") (pintype "passive"))
      (node (ref "T25") (pin "2") (pinfunction "E_2") (pintype "passive"))
      (node (ref "T26") (pin "2") (pinfunction "E_2") (pintype "passive"))
      (node (ref "T27") (pin "2") (pinfunction "E_2") (pintype "passive"))
      (node (ref "T28") (pin "2") (pinfunction "E_2") (pintype "passive"))
      (node (ref "T29") (pin "2") (pinfunction "E_2") (pintype "passive"))
      (node (ref "T3") (pin "2") (pinfunction "E_2") (pintype "passive"))
      (node (ref "T30") (pin "2") (pinfunction "E_2") (pintype "passive"))
      (node (ref "T31") (pin "2") (pinfunction "E_2") (pintype "passive"))
      (node (ref "T33") (pin "2") (pinfunction "E_2") (pintype "passive"))
      (node (ref "T35") (pin "2") (pinfunction "E_2") (pintype "passive"))
      (node (ref "T36") (pin "2") (pinfunction "E_2") (pintype "passive"))
      (node (ref "T37") (pin "2") (pinfunction "E_2") (pintype "passive"))
      (node (ref "T38") (pin "2") (pinfunction "E_2") (pintype "passive"))
      (node (ref "T4") (pin "2") (pinfunction "E_2") (pintype "passive"))
      (node (ref "T40") (pin "2") (pinfunction "E_2") (pintype "passive"))
      (node (ref "T41") (pin "2") (pinfunction "E_2") (pintype "passive"))
      (node (ref "T43") (pin "2") (pinfunction "E_2") (pintype "passive"))
      (node (ref "T44") (pin "2") (pinfunction "E_2") (pintype "passive"))
      (node (ref "T45") (pin "2") (pinfunction "E_2") (pintype "passive"))
      (node (ref "T46") (pin "2") (pinfunction "E_2") (pintype "passive"))
      (node (ref "T47") (pin "2") (pinfunction "E_2") (pintype "passive"))
      (node (ref "T48") (pin "2") (pinfunction "E_2") (pintype "passive"))
      (node (ref "T49") (pin "2") (pinfunction "E_2") (pintype "passive"))
      (node (ref "T5") (pin "2") (pinfunction "E_2") (pintype "passive"))
      (node (ref "T50") (pin "2") (pinfunction "E_2") (pintype "passive"))
      (node (ref "T51") (pin "2") (pinfunction "E_2") (pintype "passive"))
      (node (ref "T53") (pin "2") (pinfunction "E_2") (pintype "passive"))
      (node (ref "T54") (pin "2") (pinfunction "E_2") (pintype "passive"))
      (node (ref "T55") (pin "2") (pinfunction "E_2") (pintype "passive"))
      (node (ref "T56") (pin "2") (pinfunction "E_2") (pintype "passive"))
      (node (ref "T57") (pin "2") (pinfunction "E_2") (pintype "passive"))
      (node (ref "T58") (pin "2") (pinfunction "E_2") (pintype "passive"))
      (node (ref "T59") (pin "2") (pinfunction "E_2") (pintype "passive"))
      (node (ref "T6") (pin "2") (pinfunction "E_2") (pintype "passive"))
      (node (ref "T61") (pin "2") (pinfunction "E_2") (pintype "passive"))
      (node (ref "T62") (pin "2") (pinfunction "E_2") (pintype "passive"))
      (node (ref "T7") (pin "2") (pinfunction "E_2") (pintype "passive"))
      (node (ref "T9") (pin "2") (pinfunction "E_2") (pintype "passive"))
    )
    (net (code "13") (name "G_IN1") (class "Default")
      (node (ref "R153") (pin "1") (pinfunction "1_1") (pintype "passive"))
      (node (ref "R57") (pin "1") (pinfunction "1_1") (pintype "passive"))
    )
    (net (code "14") (name "G_IN2") (class "Default")
      (node (ref "R105") (pin "1") (pinfunction "1_1") (pintype "passive"))
      (node (ref "R154") (pin "1") (pinfunction "1_1") (pintype "passive"))
    )
    (net (code "15") (name "Net-(LED1-PadA)") (class "Default")
      (node (ref "LED1") (pin "A") (pinfunction "A_A") (pintype "passive"))
      (node (ref "R2") (pin "1") (pinfunction "1_1") (pintype "passive"))
    )
    (net (code "16") (name "Net-(LED2-PadA)") (class "Default")
      (node (ref "LED2") (pin "A") (pinfunction "A_A") (pintype "passive"))
      (node (ref "R6") (pin "1") (pinfunction "1_1") (pintype "passive"))
    )
    (net (code "17") (name "Net-(LED3-PadA)") (class "Default")
      (node (ref "LED3") (pin "A") (pinfunction "A_A") (pintype "passive"))
      (node (ref "R8") (pin "1") (pinfunction "1_1") (pintype "passive"))
    )
    (net (code "18") (name "Net-(LED4-PadA)") (class "Default")
      (node (ref "LED4") (pin "A") (pinfunction "A_A") (pintype "passive"))
      (node (ref "R16") (pin "1") (pinfunction "1_1") (pintype "passive"))
    )
    (net (code "19") (name "Net-(LED5-PadA)") (class "Default")
      (node (ref "LED5") (pin "A") (pinfunction "A_A") (pintype "passive"))
      (node (ref "R18") (pin "1") (pinfunction "1_1") (pintype "passive"))
    )
    (net (code "20") (name "Net-(LED6-PadA)") (class "Default")
      (node (ref "LED6") (pin "A") (pinfunction "A_A") (pintype "passive"))
      (node (ref "R26") (pin "1") (pinfunction "1_1") (pintype "passive"))
    )
    (net (code "21") (name "Net-(LED7-PadA)") (class "Default")
      (node (ref "LED7") (pin "A") (pinfunction "A_A") (pintype "passive"))
      (node (ref "R30") (pin "1") (pinfunction "1_1") (pintype "passive"))
    )
    (net (code "22") (name "Net-(LED8-PadA)") (class "Default")
      (node (ref "LED8") (pin "A") (pinfunction "A_A") (pintype "passive"))
      (node (ref "R32") (pin "1") (pinfunction "1_1") (pintype "passive"))
    )
    (net (code "23") (name "Net-(LED9-PadA)") (class "Default")
      (node (ref "LED9") (pin "A") (pinfunction "A_A") (pintype "passive"))
      (node (ref "R39") (pin "1") (pinfunction "1_1") (pintype "passive"))
    )
    (net (code "24") (name "Net-(LED10-PadA)") (class "Default")
      (node (ref "LED10") (pin "A") (pinfunction "A_A") (pintype "passive"))
      (node (ref "R41") (pin "1") (pinfunction "1_1") (pintype "passive"))
    )
    (net (code "25") (name "Net-(LED11-PadA)") (class "Default")
      (node (ref "LED11") (pin "A") (pinfunction "A_A") (pintype "passive"))
      (node (ref "R48") (pin "1") (pinfunction "1_1") (pintype "passive"))
    )
    (net (code "26") (name "Net-(LED12-PadA)") (class "Default")
      (node (ref "LED12") (pin "A") (pinfunction "A_A") (pintype "passive"))
      (node (ref "R50") (pin "1") (pinfunction "1_1") (pintype "passive"))
    )
    (net (code "27") (name "Net-(LED13-PadA)") (class "Default")
      (node (ref "LED13") (pin "A") (pinfunction "A_A") (pintype "passive"))
      (node (ref "R61") (pin "1") (pinfunction "1_1") (pintype "passive"))
    )
    (net (code "28") (name "Net-(LED14-PadA)") (class "Default")
      (node (ref "LED14") (pin "A") (pinfunction "A_A") (pintype "passive"))
      (node (ref "R64") (pin "1") (pinfunction "1_1") (pintype "passive"))
    )
    (net (code "29") (name "Net-(LED15-PadA)") (class "Default")
      (node (ref "LED15") (pin "A") (pinfunction "A_A") (pintype "passive"))
      (node (ref "R69") (pin "1") (pinfunction "1_1") (pintype "passive"))
    )
    (net (code "30") (name "Net-(LED16-PadA)") (class "Default")
      (node (ref "LED16") (pin "A") (pinfunction "A_A") (pintype "passive"))
      (node (ref "R72") (pin "1") (pinfunction "1_1") (pintype "passive"))
    )
    (net (code "31") (name "Net-(LED17-PadA)") (class "Default")
      (node (ref "LED17") (pin "A") (pinfunction "A_A") (pintype "passive"))
      (node (ref "R75") (pin "1") (pinfunction "1_1") (pintype "passive"))
    )
    (net (code "32") (name "Net-(LED18-PadA)") (class "Default")
      (node (ref "LED18") (pin "A") (pinfunction "A_A") (pintype "passive"))
      (node (ref "R77") (pin "1") (pinfunction "1_1") (pintype "passive"))
    )
    (net (code "33") (name "Net-(LED19-PadA)") (class "Default")
      (node (ref "LED19") (pin "A") (pinfunction "A_A") (pintype "passive"))
      (node (ref "R90") (pin "1") (pinfunction "1_1") (pintype "passive"))
    )
    (net (code "34") (name "Net-(LED20-PadA)") (class "Default")
      (node (ref "LED20") (pin "A") (pinfunction "A_A") (pintype "passive"))
      (node (ref "R92") (pin "1") (pinfunction "1_1") (pintype "passive"))
    )
    (net (code "35") (name "Net-(LED21-PadA)") (class "Default")
      (node (ref "LED21") (pin "A") (pinfunction "A_A") (pintype "passive"))
      (node (ref "R95") (pin "1") (pinfunction "1_1") (pintype "passive"))
    )
    (net (code "36") (name "Net-(LED22-PadA)") (class "Default")
      (node (ref "LED22") (pin "A") (pinfunction "A_A") (pintype "passive"))
      (node (ref "R97") (pin "1") (pinfunction "1_1") (pintype "passive"))
    )
    (net (code "37") (name "Net-(LED23-PadA)") (class "Default")
      (node (ref "LED23") (pin "A") (pinfunction "A_A") (pintype "passive"))
      (node (ref "R109") (pin "1") (pinfunction "1_1") (pintype "passive"))
    )
    (net (code "38") (name "Net-(LED24-PadA)") (class "Default")
      (node (ref "LED24") (pin "A") (pinfunction "A_A") (pintype "passive"))
      (node (ref "R112") (pin "1") (pinfunction "1_1") (pintype "passive"))
    )
    (net (code "39") (name "Net-(LED25-PadA)") (class "Default")
      (node (ref "LED25") (pin "A") (pinfunction "A_A") (pintype "passive"))
      (node (ref "R114") (pin "1") (pinfunction "1_1") (pintype "passive"))
    )
    (net (code "40") (name "Net-(LED26-PadA)") (class "Default")
      (node (ref "LED26") (pin "A") (pinfunction "A_A") (pintype "passive"))
      (node (ref "R117") (pin "1") (pinfunction "1_1") (pintype "passive"))
    )
    (net (code "41") (name "Net-(LED27-PadA)") (class "Default")
      (node (ref "LED27") (pin "A") (pinfunction "A_A") (pintype "passive"))
      (node (ref "R126") (pin "1") (pinfunction "1_1") (pintype "passive"))
    )
    (net (code "42") (name "Net-(LED28-PadA)") (class "Default")
      (node (ref "LED28") (pin "A") (pinfunction "A_A") (pintype "passive"))
      (node (ref "R130") (pin "1") (pinfunction "1_1") (pintype "passive"))
    )
    (net (code "43") (name "Net-(LED29-PadA)") (class "Default")
      (node (ref "LED29") (pin "A") (pinfunction "A_A") (pintype "passive"))
      (node (ref "R133") (pin "1") (pinfunction "1_1") (pintype "passive"))
    )
    (net (code "44") (name "Net-(LED30-PadA)") (class "Default")
      (node (ref "LED30") (pin "A") (pinfunction "A_A") (pintype "passive"))
      (node (ref "R135") (pin "1") (pinfunction "1_1") (pintype "passive"))
    )
    (net (code "45") (name "Net-(LED31-PadA)") (class "Default")
      (node (ref "LED31") (pin "A") (pinfunction "A_A") (pintype "passive"))
      (node (ref "R144") (pin "1") (pinfunction "1_1") (pintype "passive"))
    )
    (net (code "46") (name "Net-(LED32-PadA)") (class "Default")
      (node (ref "LED32") (pin "A") (pinfunction "A_A") (pintype "passive"))
      (node (ref "R146") (pin "1") (pinfunction "1_1") (pintype "passive"))
    )
    (net (code "47") (name "Net-(LED33-PadA)") (class "Default")
      (node (ref "LED33") (pin "A") (pinfunction "A_A") (pintype "passive"))
      (node (ref "R156") (pin "1") (pinfunction "1_1") (pintype "passive"))
    )
    (net (code "48") (name "Net-(LED34-PadA)") (class "Default")
      (node (ref "LED34") (pin "A") (pinfunction "A_A") (pintype "passive"))
      (node (ref "R158") (pin "1") (pinfunction "1_1") (pintype "passive"))
    )
    (net (code "49") (name "Net-(R4-Pad1)") (class "Default")
      (node (ref "R4") (pin "1") (pinfunction "1_1") (pintype "passive"))
      (node (ref "R9") (pin "2") (pinfunction "2_2") (pintype "passive"))
    )
    (net (code "50") (name "Net-(R12-Pad1)") (class "Default")
      (node (ref "R12") (pin "1") (pinfunction "1_1") (pintype "passive"))
      (node (ref "R21") (pin "2") (pinfunction "2_2") (pintype "passive"))
    )
    (net (code "51") (name "Net-(R13-Pad1)") (class "Default")
      (node (ref "R13") (pin "1") (pinfunction "1_1") (pintype "passive"))
      (node (ref "R19") (pin "2") (pinfunction "2_2") (pintype "passive"))
    )
    (net (code "52") (name "Net-(R14-Pad1)") (class "Default")
      (node (ref "R14") (pin "1") (pinfunction "1_1") (pintype "passive"))
      (node (ref "R20") (pin "2") (pinfunction "2_2") (pintype "passive"))
    )
    (net (code "53") (name "Net-(R28-Pad1)") (class "Default")
      (node (ref "R28") (pin "1") (pinfunction "1_1") (pintype "passive"))
      (node (ref "R33") (pin "2") (pinfunction "2_2") (pintype "passive"))
    )
    (net (code "54") (name "Net-(R36-Pad1)") (class "Default")
      (node (ref "R36") (pin "1") (pinfunction "1_1") (pintype "passive"))
      (node (ref "R43") (pin "2") (pinfunction "2_2") (pintype "passive"))
    )
    (net (code "55") (name "Net-(R37-Pad1)") (class "Default")
      (node (ref "R37") (pin "1") (pinfunction "1_1") (pintype "passive"))
      (node (ref "R42") (pin "2") (pinfunction "2_2") (pintype "passive"))
    )
    (net (code "56") (name "Net-(R53-Pad1)") (class "Default")
      (node (ref "R53") (pin "1") (pinfunction "1_1") (pintype "passive"))
      (node (ref "R56") (pin "2") (pinfunction "2_2") (pintype "passive"))
    )
    (net (code "57") (name "Net-(R54-Pad1)") (class "Default")
      (node (ref "R54") (pin "1") (pinfunction "1_1") (pintype "passive"))
      (node (ref "R55") (pin "2") (pinfunction "2_2") (pintype "passive"))
    )
    (net (code "58") (name "Net-(R57-Pad2)") (class "Default")
      (node (ref "R57") (pin "2") (pinfunction "2_2") (pintype "passive"))
      (node (ref "R58") (pin "2") (pinfunction "2_2") (pintype "passive"))
    )
    (net (code "59") (name "Net-(R58-Pad1)") (class "Default")
      (node (ref "R58") (pin "1") (pinfunction "1_1") (pintype "passive"))
      (node (ref "R59") (pin "1") (pinfunction "1_1") (pintype "passive"))
    )
    (net (code "60") (name "Net-(R59-Pad2)") (class "Default")
      (node (ref "R59") (pin "2") (pinfunction "2_2") (pintype "passive"))
      (node (ref "R62") (pin "2") (pinfunction "2_2") (pintype "passive"))
    )
    (net (code "61") (name "Net-(R62-Pad1)") (class "Default")
      (node (ref "R62") (pin "1") (pinfunction "1_1") (pintype "passive"))
      (node (ref "R65") (pin "1") (pinfunction "1_1") (pintype "passive"))
    )
    (net (code "62") (name "Net-(R79-Pad1)") (class "Default")
      (node (ref "R79") (pin "1") (pinfunction "1_1") (pintype "passive"))
      (node (ref "R82") (pin "2") (pinfunction "2_2") (pintype "passive"))
    )
    (net (code "63") (name "Net-(R80-Pad1)") (class "Default")
      (node (ref "R80") (pin "1") (pinfunction "1_1") (pintype "passive"))
      (node (ref "R83") (pin "2") (pinfunction "2_2") (pintype "passive"))
    )
    (net (code "64") (name "Net-(R81-Pad1)") (class "Default")
      (node (ref "R81") (pin "1") (pinfunction "1_1") (pintype "passive"))
      (node (ref "R84") (pin "2") (pinfunction "2_2") (pintype "passive"))
    )
    (net (code "65") (name "Net-(R102-Pad2)") (class "Default")
      (node (ref "R102") (pin "2") (pinfunction "2_2") (pintype "passive"))
      (node (ref "R99") (pin "1") (pinfunction "1_1") (pintype "passive"))
    )
    (net (code "66") (name "Net-(R103-Pad2)") (class "Default")
      (node (ref "R103") (pin "2") (pinfunction "2_2") (pintype "passive"))
      (node (ref "R104") (pin "1") (pinfunction "1_1") (pintype "passive"))
    )
    (net (code "67") (name "Net-(R105-Pad2)") (class "Default")
      (node (ref "R105") (pin "2") (pinfunction "2_2") (pintype "passive"))
      (node (ref "R106") (pin "1") (pinfunction "1_1") (pintype "passive"))
    )
    (net (code "68") (name "Net-(R106-Pad2)") (class "Default")
      (node (ref "R106") (pin "2") (pinfunction "2_2") (pintype "passive"))
      (node (ref "R107") (pin "2") (pinfunction "2_2") (pintype "passive"))
    )
    (net (code "69") (name "Net-(R107-Pad1)") (class "Default")
      (node (ref "R107") (pin "1") (pinfunction "1_1") (pintype "passive"))
      (node (ref "R110") (pin "2") (pinfunction "2_2") (pintype "passive"))
    )
    (net (code "70") (name "Net-(R110-Pad1)") (class "Default")
      (node (ref "R110") (pin "1") (pinfunction "1_1") (pintype "passive"))
      (node (ref "R115") (pin "1") (pinfunction "1_1") (pintype "passive"))
    )
    (net (code "71") (name "Net-(R123-Pad1)") (class "Default")
      (node (ref "R123") (pin "1") (pinfunction "1_1") (pintype "passive"))
      (node (ref "R127") (pin "2") (pinfunction "2_2") (pintype "passive"))
    )
    (net (code "72") (name "Net-(R124-Pad1)") (class "Default")
      (node (ref "R124") (pin "1") (pinfunction "1_1") (pintype "passive"))
      (node (ref "R128") (pin "2") (pinfunction "2_2") (pintype "passive"))
    )
    (net (code "73") (name "Net-(R137-Pad1)") (class "Default")
      (node (ref "R137") (pin "1") (pinfunction "1_1") (pintype "passive"))
      (node (ref "R140") (pin "2") (pinfunction "2_2") (pintype "passive"))
    )
    (net (code "74") (name "Net-(R141-Pad2)") (class "Default")
      (node (ref "R141") (pin "2") (pinfunction "2_2") (pintype "passive"))
      (node (ref "R142") (pin "1") (pinfunction "1_1") (pintype "passive"))
    )
    (net (code "75") (name "Net-(R149-Pad1)") (class "Default")
      (node (ref "R149") (pin "1") (pinfunction "1_1") (pintype "passive"))
      (node (ref "R152") (pin "2") (pinfunction "2_2") (pintype "passive"))
    )
    (net (code "76") (name "Net-(R150-Pad1)") (class "Default")
      (node (ref "R150") (pin "1") (pinfunction "1_1") (pintype "passive"))
      (node (ref "R153") (pin "2") (pinfunction "2_2") (pintype "passive"))
    )
    (net (code "77") (name "Net-(R151-Pad1)") (class "Default")
      (node (ref "R151") (pin "1") (pinfunction "1_1") (pintype "passive"))
      (node (ref "R154") (pin "2") (pinfunction "2_2") (pintype "passive"))
    )
    (net (code "78") (name "Net-(R162-Pad2)") (class "Default")
      (node (ref "R162") (pin "2") (pinfunction "2_2") (pintype "passive"))
      (node (ref "R163") (pin "1") (pinfunction "1_1") (pintype "passive"))
    )
    (net (code "79") (name "Net-(R164-Pad2)") (class "Default")
      (node (ref "R164") (pin "2") (pinfunction "2_2") (pintype "passive"))
      (node (ref "R165") (pin "1") (pinfunction "1_1") (pintype "passive"))
    )
    (net (code "80") (name "Net-(R167-Pad2)") (class "Default")
      (node (ref "R167") (pin "2") (pinfunction "2_2") (pintype "passive"))
      (node (ref "R168") (pin "1") (pinfunction "1_1") (pintype "passive"))
    )
    (net (code "81") (name "Net-(R171-Pad2)") (class "Default")
      (node (ref "R171") (pin "2") (pinfunction "2_2") (pintype "passive"))
      (node (ref "R172") (pin "1") (pinfunction "1_1") (pintype "passive"))
    )
    (net (code "82") (name "Net-(R173-Pad2)") (class "Default")
      (node (ref "R173") (pin "2") (pinfunction "2_2") (pintype "passive"))
      (node (ref "R174") (pin "1") (pinfunction "1_1") (pintype "passive"))
    )
    (net (code "83") (name "Net-(R175-Pad2)") (class "Default")
      (node (ref "R175") (pin "2") (pinfunction "2_2") (pintype "passive"))
      (node (ref "R176") (pin "1") (pinfunction "1_1") (pintype "passive"))
    )
    (net (code "84") (name "Net-(R178-Pad2)") (class "Default")
      (node (ref "R178") (pin "2") (pinfunction "2_2") (pintype "passive"))
      (node (ref "R179") (pin "1") (pinfunction "1_1") (pintype "passive"))
    )
    (net (code "85") (name "Net-(R181-Pad2)") (class "Default")
      (node (ref "R181") (pin "2") (pinfunction "2_2") (pintype "passive"))
      (node (ref "R182") (pin "1") (pinfunction "1_1") (pintype "passive"))
    )
    (net (code "86") (name "Net-(R185-Pad2)") (class "Default")
      (node (ref "R185") (pin "2") (pinfunction "2_2") (pintype "passive"))
      (node (ref "R186") (pin "1") (pinfunction "1_1") (pintype "passive"))
    )
    (net (code "87") (name "Net-(R191-Pad2)") (class "Default")
      (node (ref "R191") (pin "2") (pinfunction "2_2") (pintype "passive"))
      (node (ref "R192") (pin "1") (pinfunction "1_1") (pintype "passive"))
    )
    (net (code "88") (name "Net-(R194-Pad2)") (class "Default")
      (node (ref "R194") (pin "2") (pinfunction "2_2") (pintype "passive"))
      (node (ref "R195") (pin "1") (pinfunction "1_1") (pintype "passive"))
    )
    (net (code "89") (name "Net-(R196-Pad2)") (class "Default")
      (node (ref "R196") (pin "2") (pinfunction "2_2") (pintype "passive"))
      (node (ref "R197") (pin "1") (pinfunction "1_1") (pintype "passive"))
    )
    (net (code "90") (name "Net-(R198-Pad2)") (class "Default")
      (node (ref "R198") (pin "2") (pinfunction "2_2") (pintype "passive"))
      (node (ref "R199") (pin "1") (pinfunction "1_1") (pintype "passive"))
    )
    (net (code "91") (name "Net-(R238-Pad2)") (class "Default")
      (node (ref "R238") (pin "2") (pinfunction "2_2") (pintype "passive"))
      (node (ref "R239") (pin "1") (pinfunction "1_1") (pintype "passive"))
    )
    (net (code "92") (name "Net-(R241-Pad2)") (class "Default")
      (node (ref "R241") (pin "2") (pinfunction "2_2") (pintype "passive"))
      (node (ref "R242") (pin "1") (pinfunction "1_1") (pintype "passive"))
    )
    (net (code "93") (name "Net-(R244-Pad2)") (class "Default")
      (node (ref "R244") (pin "2") (pinfunction "2_2") (pintype "passive"))
      (node (ref "R245") (pin "1") (pinfunction "1_1") (pintype "passive"))
    )
    (net (code "94") (name "Net-(T1-B)") (class "Default")
      (node (ref "R3") (pin "2") (pinfunction "2_2") (pintype "passive"))
      (node (ref "T1") (pin "1") (pinfunction "B_1") (pintype "passive"))
    )
    (net (code "95") (name "Net-(T1-C)") (class "Default")
      (node (ref "LED1") (pin "C") (pinfunction "C_C") (pintype "passive"))
      (node (ref "R1") (pin "1") (pinfunction "1_1") (pintype "passive"))
      (node (ref "R11") (pin "1") (pinfunction "1_1") (pintype "passive"))
      (node (ref "T1") (pin "3") (pinfunction "C_3") (pintype "passive"))
      (node (ref "T2") (pin "3") (pinfunction "C_3") (pintype "passive"))
    )
    (net (code "96") (name "Net-(T2-B)") (class "Default")
      (node (ref "R4") (pin "2") (pinfunction "2_2") (pintype "passive"))
      (node (ref "T2") (pin "1") (pinfunction "B_1") (pintype "passive"))
    )
    (net (code "97") (name "Net-(T3-B)") (class "Default")
      (node (ref "R10") (pin "2") (pinfunction "2_2") (pintype "passive"))
      (node (ref "T3") (pin "1") (pinfunction "B_1") (pintype "passive"))
    )
    (net (code "98") (name "Net-(T4-B)") (class "Default")
      (node (ref "R11") (pin "2") (pinfunction "2_2") (pintype "passive"))
      (node (ref "T4") (pin "1") (pinfunction "B_1") (pintype "passive"))
    )
    (net (code "99") (name "Net-(T4-C)") (class "Default")
      (node (ref "LED3") (pin "C") (pinfunction "C_C") (pintype "passive"))
      (node (ref "R10") (pin "1") (pinfunction "1_1") (pintype "passive"))
      (node (ref "R7") (pin "1") (pinfunction "1_1") (pintype "passive"))
      (node (ref "T4") (pin "3") (pinfunction "C_3") (pintype "passive"))
      (node (ref "T5") (pin "3") (pinfunction "C_3") (pintype "passive"))
      (node (ref "T6") (pin "3") (pinfunction "C_3") (pintype "passive"))
      (node (ref "T7") (pin "3") (pinfunction "C_3") (pintype "passive"))
    )
    (net (code "100") (name "Net-(T5-B)") (class "Default")
      (node (ref "R12") (pin "2") (pinfunction "2_2") (pintype "passive"))
      (node (ref "T5") (pin "1") (pinfunction "B_1") (pintype "passive"))
    )
    (net (code "101") (name "Net-(T6-B)") (class "Default")
      (node (ref "R13") (pin "2") (pinfunction "2_2") (pintype "passive"))
      (node (ref "T6") (pin "1") (pinfunction "B_1") (pintype "passive"))
    )
    (net (code "102") (name "Net-(T7-B)") (class "Default")
      (node (ref "R14") (pin "2") (pinfunction "2_2") (pintype "passive"))
      (node (ref "T7") (pin "1") (pinfunction "B_1") (pintype "passive"))
    )
    (net (code "103") (name "Net-(T8-B)") (class "Default")
      (node (ref "R22") (pin "2") (pinfunction "2_2") (pintype "passive"))
      (node (ref "T8") (pin "1") (pinfunction "B_1") (pintype "passive"))
    )
    (net (code "104") (name "Net-(T8-C)") (class "Default")
      (node (ref "LED4") (pin "C") (pinfunction "C_C") (pintype "passive"))
      (node (ref "R15") (pin "1") (pinfunction "1_1") (pintype "passive"))
      (node (ref "R23") (pin "1") (pinfunction "1_1") (pintype "passive"))
      (node (ref "T8") (pin "3") (pinfunction "C_3") (pintype "passive"))
    )
    (net (code "105") (name "Net-(T9-B)") (class "Default")
      (node (ref "R23") (pin "2") (pinfunction "2_2") (pintype "passive"))
      (node (ref "T9") (pin "1") (pinfunction "B_1") (pintype "passive"))
    )
    (net (code "106") (name "Net-(T9-C)") (class "Default")
      (node (ref "LED5") (pin "C") (pinfunction "C_C") (pintype "passive"))
      (node (ref "R17") (pin "1") (pinfunction "1_1") (pintype "passive"))
      (node (ref "R21") (pin "1") (pinfunction "1_1") (pintype "passive"))
      (node (ref "T9") (pin "3") (pinfunction "C_3") (pintype "passive"))
    )
    (net (code "107") (name "Net-(T10-B)") (class "Default")
      (node (ref "R24") (pin "2") (pinfunction "2_2") (pintype "passive"))
      (node (ref "T10") (pin "1") (pinfunction "B_1") (pintype "passive"))
    )
    (net (code "108") (name "Net-(T10-C)") (class "Default")
      (node (ref "T10") (pin "3") (pinfunction "C_3") (pintype "passive"))
      (node (ref "T8") (pin "2") (pinfunction "E_2") (pintype "passive"))
    )
    (net (code "109") (name "Net-(T11-B)") (class "Default")
      (node (ref "R27") (pin "2") (pinfunction "2_2") (pintype "passive"))
      (node (ref "T11") (pin "1") (pinfunction "B_1") (pintype "passive"))
    )
    (net (code "110") (name "Net-(T11-C)") (class "Default")
      (node (ref "LED6") (pin "C") (pinfunction "C_C") (pintype "passive"))
      (node (ref "R25") (pin "1") (pinfunction "1_1") (pintype "passive"))
      (node (ref "R35") (pin "1") (pinfunction "1_1") (pintype "passive"))
      (node (ref "T11") (pin "3") (pinfunction "C_3") (pintype "passive"))
      (node (ref "T12") (pin "3") (pinfunction "C_3") (pintype "passive"))
    )
    (net (code "111") (name "Net-(T12-B)") (class "Default")
      (node (ref "R28") (pin "2") (pinfunction "2_2") (pintype "passive"))
      (node (ref "T12") (pin "1") (pinfunction "B_1") (pintype "passive"))
    )
    (net (code "112") (name "Net-(T13-B)") (class "Default")
      (node (ref "R34") (pin "2") (pinfunction "2_2") (pintype "passive"))
      (node (ref "T13") (pin "1") (pinfunction "B_1") (pintype "passive"))
    )
    (net (code "113") (name "Net-(T14-B)") (class "Default")
      (node (ref "R35") (pin "2") (pinfunction "2_2") (pintype "passive"))
      (node (ref "T14") (pin "1") (pinfunction "B_1") (pintype "passive"))
    )
    (net (code "114") (name "Net-(T14-C)") (class "Default")
      (node (ref "LED8") (pin "C") (pinfunction "C_C") (pintype "passive"))
      (node (ref "R31") (pin "1") (pinfunction "1_1") (pintype "passive"))
      (node (ref "R34") (pin "1") (pinfunction "1_1") (pintype "passive"))
      (node (ref "T14") (pin "3") (pinfunction "C_3") (pintype "passive"))
      (node (ref "T15") (pin "3") (pinfunction "C_3") (pintype "passive"))
      (node (ref "T16") (pin "3") (pinfunction "C_3") (pintype "passive"))
    )
    (net (code "115") (name "Net-(T15-B)") (class "Default")
      (node (ref "R36") (pin "2") (pinfunction "2_2") (pintype "passive"))
      (node (ref "T15") (pin "1") (pinfunction "B_1") (pintype "passive"))
    )
    (net (code "116") (name "Net-(T16-B)") (class "Default")
      (node (ref "R37") (pin "2") (pinfunction "2_2") (pintype "passive"))
      (node (ref "T16") (pin "1") (pinfunction "B_1") (pintype "passive"))
    )
    (net (code "117") (name "Net-(T17-B)") (class "Default")
      (node (ref "R44") (pin "2") (pinfunction "2_2") (pintype "passive"))
      (node (ref "T17") (pin "1") (pinfunction "B_1") (pintype "passive"))
    )
    (net (code "118") (name "Net-(T17-C)") (class "Default")
      (node (ref "LED9") (pin "C") (pinfunction "C_C") (pintype "passive"))
      (node (ref "R38") (pin "1") (pinfunction "1_1") (pintype "passive"))
      (node (ref "R45") (pin "1") (pinfunction "1_1") (pintype "passive"))
      (node (ref "T17") (pin "3") (pinfunction "C_3") (pintype "passive"))
    )
    (net (code "119") (name "Net-(T17-E)") (class "Default")
      (node (ref "T17") (pin "2") (pinfunction "E_2") (pintype "passive"))
      (node (ref "T19") (pin "3") (pinfunction "C_3") (pintype "passive"))
    )
    (net (code "120") (name "Net-(T18-B)") (class "Default")
      (node (ref "R45") (pin "2") (pinfunction "2_2") (pintype "passive"))
      (node (ref "T18") (pin "1") (pinfunction "B_1") (pintype "passive"))
    )
    (net (code "121") (name "Net-(T18-C)") (class "Default")
      (node (ref "LED10") (pin "C") (pinfunction "C_C") (pintype "passive"))
      (node (ref "R40") (pin "1") (pinfunction "1_1") (pintype "passive"))
      (node (ref "R43") (pin "1") (pinfunction "1_1") (pintype "passive"))
      (node (ref "T18") (pin "3") (pinfunction "C_3") (pintype "passive"))
    )
    (net (code "122") (name "Net-(T19-B)") (class "Default")
      (node (ref "R46") (pin "2") (pinfunction "2_2") (pintype "passive"))
      (node (ref "T19") (pin "1") (pinfunction "B_1") (pintype "passive"))
    )
    (net (code "123") (name "Net-(T20-B)") (class "Default")
      (node (ref "R51") (pin "2") (pinfunction "2_2") (pintype "passive"))
      (node (ref "T20") (pin "1") (pinfunction "B_1") (pintype "passive"))
    )
    (net (code "124") (name "Net-(T21-B)") (class "Default")
      (node (ref "R52") (pin "2") (pinfunction "2_2") (pintype "passive"))
      (node (ref "T21") (pin "1") (pinfunction "B_1") (pintype "passive"))
    )
    (net (code "125") (name "Net-(T21-C)") (class "Default")
      (node (ref "LED12") (pin "C") (pinfunction "C_C") (pintype "passive"))
      (node (ref "R49") (pin "1") (pinfunction "1_1") (pintype "passive"))
      (node (ref "R51") (pin "1") (pinfunction "1_1") (pintype "passive"))
      (node (ref "T21") (pin "3") (pinfunction "C_3") (pintype "passive"))
      (node (ref "T22") (pin "3") (pinfunction "C_3") (pintype "passive"))
      (node (ref "T23") (pin "3") (pinfunction "C_3") (pintype "passive"))
    )
    (net (code "126") (name "Net-(T22-B)") (class "Default")
      (node (ref "R53") (pin "2") (pinfunction "2_2") (pintype "passive"))
      (node (ref "T22") (pin "1") (pinfunction "B_1") (pintype "passive"))
    )
    (net (code "127") (name "Net-(T23-B)") (class "Default")
      (node (ref "R54") (pin "2") (pinfunction "2_2") (pintype "passive"))
      (node (ref "T23") (pin "1") (pinfunction "B_1") (pintype "passive"))
    )
    (net (code "128") (name "Net-(T24-B)") (class "Default")
      (node (ref "R66") (pin "2") (pinfunction "2_2") (pintype "passive"))
      (node (ref "T24") (pin "1") (pinfunction "B_1") (pintype "passive"))
    )
    (net (code "129") (name "Net-(T24-C)") (class "Default")
      (node (ref "LED13") (pin "C") (pinfunction "C_C") (pintype "passive"))
      (node (ref "R60") (pin "1") (pinfunction "1_1") (pintype "passive"))
      (node (ref "R67") (pin "1") (pinfunction "1_1") (pintype "passive"))
      (node (ref "T24") (pin "3") (pinfunction "C_3") (pintype "passive"))
    )
    (net (code "130") (name "Net-(T24-E)") (class "Default")
      (node (ref "T24") (pin "2") (pinfunction "E_2") (pintype "passive"))
      (node (ref "T26") (pin "3") (pinfunction "C_3") (pintype "passive"))
    )
    (net (code "131") (name "Net-(T25-B)") (class "Default")
      (node (ref "R67") (pin "2") (pinfunction "2_2") (pintype "passive"))
      (node (ref "T25") (pin "1") (pinfunction "B_1") (pintype "passive"))
    )
    (net (code "132") (name "Net-(T25-C)") (class "Default")
      (node (ref "LED14") (pin "C") (pinfunction "C_C") (pintype "passive"))
      (node (ref "R63") (pin "1") (pinfunction "1_1") (pintype "passive"))
      (node (ref "R65") (pin "2") (pinfunction "2_2") (pintype "passive"))
      (node (ref "R78") (pin "1") (pinfunction "1_1") (pintype "passive"))
      (node (ref "T25") (pin "3") (pinfunction "C_3") (pintype "passive"))
    )
    (net (code "133") (name "Net-(T26-B)") (class "Default")
      (node (ref "R70") (pin "2") (pinfunction "2_2") (pintype "passive"))
      (node (ref "T26") (pin "1") (pinfunction "B_1") (pintype "passive"))
    )
    (net (code "134") (name "Net-(T27-B)") (class "Default")
      (node (ref "R73") (pin "2") (pinfunction "2_2") (pintype "passive"))
      (node (ref "T27") (pin "1") (pinfunction "B_1") (pintype "passive"))
    )
    (net (code "135") (name "Net-(T28-B)") (class "Default")
      (node (ref "R78") (pin "2") (pinfunction "2_2") (pintype "passive"))
      (node (ref "T28") (pin "1") (pinfunction "B_1") (pintype "passive"))
    )
    (net (code "136") (name "Net-(T28-C)") (class "Default")
      (node (ref "LED16") (pin "C") (pinfunction "C_C") (pintype "passive"))
      (node (ref "R71") (pin "1") (pinfunction "1_1") (pintype "passive"))
      (node (ref "R73") (pin "1") (pinfunction "1_1") (pintype "passive"))
      (node (ref "T28") (pin "3") (pinfunction "C_3") (pintype "passive"))
      (node (ref "T29") (pin "3") (pinfunction "C_3") (pintype "passive"))
      (node (ref "T30") (pin "3") (pinfunction "C_3") (pintype "passive"))
      (node (ref "T31") (pin "3") (pinfunction "C_3") (pintype "passive"))
    )
    (net (code "137") (name "Net-(T29-B)") (class "Default")
      (node (ref "R79") (pin "2") (pinfunction "2_2") (pintype "passive"))
      (node (ref "T29") (pin "1") (pinfunction "B_1") (pintype "passive"))
    )
    (net (code "138") (name "Net-(T30-B)") (class "Default")
      (node (ref "R80") (pin "2") (pinfunction "2_2") (pintype "passive"))
      (node (ref "T30") (pin "1") (pinfunction "B_1") (pintype "passive"))
    )
    (net (code "139") (name "Net-(T31-B)") (class "Default")
      (node (ref "R81") (pin "2") (pinfunction "2_2") (pintype "passive"))
      (node (ref "T31") (pin "1") (pinfunction "B_1") (pintype "passive"))
    )
    (net (code "140") (name "Net-(T32-B)") (class "Default")
      (node (ref "R85") (pin "2") (pinfunction "2_2") (pintype "passive"))
      (node (ref "T32") (pin "1") (pinfunction "B_1") (pintype "passive"))
    )
    (net (code "141") (name "Net-(T32-C)") (class "Default")
      (node (ref "LED17") (pin "C") (pinfunction "C_C") (pintype "passive"))
      (node (ref "R74") (pin "1") (pinfunction "1_1") (pintype "passive"))
      (node (ref "R86") (pin "1") (pinfunction "1_1") (pintype "passive"))
      (node (ref "T32") (pin "3") (pinfunction "C_3") (pintype "passive"))
    )
    (net (code "142") (name "Net-(T32-E)") (class "Default")
      (node (ref "T32") (pin "2") (pinfunction "E_2") (pintype "passive"))
      (node (ref "T34") (pin "3") (pinfunction "C_3") (pintype "passive"))
    )
    (net (code "143") (name "Net-(T33-B)") (class "Default")
      (node (ref "R86") (pin "2") (pinfunction "2_2") (pintype "passive"))
      (node (ref "T33") (pin "1") (pinfunction "B_1") (pintype "passive"))
    )
    (net (code "144") (name "Net-(T33-C)") (class "Default")
      (node (ref "LED18") (pin "C") (pinfunction "C_C") (pintype "passive"))
      (node (ref "R76") (pin "1") (pinfunction "1_1") (pintype "passive"))
      (node (ref "R82") (pin "1") (pinfunction "1_1") (pintype "passive"))
      (node (ref "T33") (pin "3") (pinfunction "C_3") (pintype "passive"))
    )
    (net (code "145") (name "Net-(T34-B)") (class "Default")
      (node (ref "R87") (pin "2") (pinfunction "2_2") (pintype "passive"))
      (node (ref "T34") (pin "1") (pinfunction "B_1") (pintype "passive"))
    )
    (net (code "146") (name "Net-(T34-E)") (class "Default")
      (node (ref "T34") (pin "2") (pinfunction "E_2") (pintype "passive"))
      (node (ref "T35") (pin "3") (pinfunction "C_3") (pintype "passive"))
    )
    (net (code "147") (name "Net-(T35-B)") (class "Default")
      (node (ref "R88") (pin "2") (pinfunction "2_2") (pintype "passive"))
      (node (ref "T35") (pin "1") (pinfunction "B_1") (pintype "passive"))
    )
    (net (code "148") (name "Net-(T36-B)") (class "Default")
      (node (ref "R93") (pin "2") (pinfunction "2_2") (pintype "passive"))
      (node (ref "T36") (pin "1") (pinfunction "B_1") (pintype "passive"))
    )
    (net (code "149") (name "Net-(T36-C)") (class "Default")
      (node (ref "LED19") (pin "C") (pinfunction "C_C") (pintype "passive"))
      (node (ref "R100") (pin "1") (pinfunction "1_1") (pintype "passive"))
      (node (ref "R89") (pin "1") (pinfunction "1_1") (pintype "passive"))
      (node (ref "T36") (pin "3") (pinfunction "C_3") (pintype "passive"))
    )
    (net (code "150") (name "Net-(T37-B)") (class "Default")
      (node (ref "R98") (pin "2") (pinfunction "2_2") (pintype "passive"))
      (node (ref "T37") (pin "1") (pinfunction "B_1") (pintype "passive"))
    )
    (net (code "151") (name "Net-(T37-C)") (class "Default")
      (node (ref "LED20") (pin "C") (pinfunction "C_C") (pintype "passive"))
      (node (ref "R91") (pin "1") (pinfunction "1_1") (pintype "passive"))
      (node (ref "R93") (pin "1") (pinfunction "1_1") (pintype "passive"))
      (node (ref "T37") (pin "3") (pinfunction "C_3") (pintype "passive"))
      (node (ref "T38") (pin "3") (pinfunction "C_3") (pintype "passive"))
    )
    (net (code "152") (name "Net-(T38-B)") (class "Default")
      (node (ref "R99") (pin "2") (pinfunction "2_2") (pintype "passive"))
      (node (ref "T38") (pin "1") (pinfunction "B_1") (pintype "passive"))
    )
    (net (code "153") (name "Net-(T39-B)") (class "Default")
      (node (ref "R100") (pin "2") (pinfunction "2_2") (pintype "passive"))
      (node (ref "T39") (pin "1") (pinfunction "B_1") (pintype "passive"))
    )
    (net (code "154") (name "Net-(T39-C)") (class "Default")
      (node (ref "LED21") (pin "C") (pinfunction "C_C") (pintype "passive"))
      (node (ref "R101") (pin "1") (pinfunction "1_1") (pintype "passive"))
      (node (ref "R94") (pin "1") (pinfunction "1_1") (pintype "passive"))
      (node (ref "T39") (pin "3") (pinfunction "C_3") (pintype "passive"))
    )
    (net (code "155") (name "Net-(T39-E)") (class "Default")
      (node (ref "T39") (pin "2") (pinfunction "E_2") (pintype "passive"))
      (node (ref "T41") (pin "3") (pinfunction "C_3") (pintype "passive"))
    )
    (net (code "156") (name "Net-(T40-B)") (class "Default")
      (node (ref "R101") (pin "2") (pinfunction "2_2") (pintype "passive"))
      (node (ref "T40") (pin "1") (pinfunction "B_1") (pintype "passive"))
    )
    (net (code "157") (name "Net-(T41-B)") (class "Default")
      (node (ref "R104") (pin "2") (pinfunction "2_2") (pintype "passive"))
      (node (ref "T41") (pin "1") (pinfunction "B_1") (pintype "passive"))
    )
    (net (code "158") (name "Net-(T42-B)") (class "Default")
      (node (ref "R118") (pin "2") (pinfunction "2_2") (pintype "passive"))
      (node (ref "T42") (pin "1") (pinfunction "B_1") (pintype "passive"))
    )
    (net (code "159") (name "Net-(T42-C)") (class "Default")
      (node (ref "LED23") (pin "C") (pinfunction "C_C") (pintype "passive"))
      (node (ref "R108") (pin "1") (pinfunction "1_1") (pintype "passive"))
      (node (ref "R119") (pin "1") (pinfunction "1_1") (pintype "passive"))
      (node (ref "T42") (pin "3") (pinfunction "C_3") (pintype "passive"))
    )
    (net (code "160") (name "Net-(T42-E)") (class "Default")
      (node (ref "T42") (pin "2") (pinfunction "E_2") (pintype "passive"))
      (node (ref "T45") (pin "3") (pinfunction "C_3") (pintype "passive"))
    )
    (net (code "161") (name "Net-(T43-B)") (class "Default")
      (node (ref "R119") (pin "2") (pinfunction "2_2") (pintype "passive"))
      (node (ref "T43") (pin "1") (pinfunction "B_1") (pintype "passive"))
    )
    (net (code "162") (name "Net-(T43-C)") (class "Default")
      (node (ref "LED24") (pin "C") (pinfunction "C_C") (pintype "passive"))
      (node (ref "R111") (pin "1") (pinfunction "1_1") (pintype "passive"))
      (node (ref "R115") (pin "2") (pinfunction "2_2") (pintype "passive"))
      (node (ref "R122") (pin "1") (pinfunction "1_1") (pintype "passive"))
      (node (ref "T43") (pin "3") (pinfunction "C_3") (pintype "passive"))
    )
    (net (code "163") (name "Net-(T44-B)") (class "Default")
      (node (ref "R120") (pin "2") (pinfunction "2_2") (pintype "passive"))
      (node (ref "T44") (pin "1") (pinfunction "B_1") (pintype "passive"))
    )
    (net (code "164") (name "Net-(T45-B)") (class "Default")
      (node (ref "R121") (pin "2") (pinfunction "2_2") (pintype "passive"))
      (node (ref "T45") (pin "1") (pinfunction "B_1") (pintype "passive"))
    )
    (net (code "165") (name "Net-(T46-B)") (class "Default")
      (node (ref "R122") (pin "2") (pinfunction "2_2") (pintype "passive"))
      (node (ref "T46") (pin "1") (pinfunction "B_1") (pintype "passive"))
    )
    (net (code "166") (name "Net-(T46-C)") (class "Default")
      (node (ref "LED26") (pin "C") (pinfunction "C_C") (pintype "passive"))
      (node (ref "R116") (pin "1") (pinfunction "1_1") (pintype "passive"))
      (node (ref "R120") (pin "1") (pinfunction "1_1") (pintype "passive"))
      (node (ref "T46") (pin "3") (pinfunction "C_3") (pintype "passive"))
      (node (ref "T47") (pin "3") (pinfunction "C_3") (pintype "passive"))
      (node (ref "T48") (pin "3") (pinfunction "C_3") (pintype "passive"))
    )
    (net (code "167") (name "Net-(T47-B)") (class "Default")
      (node (ref "R123") (pin "2") (pinfunction "2_2") (pintype "passive"))
      (node (ref "T47") (pin "1") (pinfunction "B_1") (pintype "passive"))
    )
    (net (code "168") (name "Net-(T48-B)") (class "Default")
      (node (ref "R124") (pin "2") (pinfunction "2_2") (pintype "passive"))
      (node (ref "T48") (pin "1") (pinfunction "B_1") (pintype "passive"))
    )
    (net (code "169") (name "Net-(T49-B)") (class "Default")
      (node (ref "R131") (pin "2") (pinfunction "2_2") (pintype "passive"))
      (node (ref "T49") (pin "1") (pinfunction "B_1") (pintype "passive"))
    )
    (net (code "170") (name "Net-(T49-C)") (class "Default")
      (node (ref "LED27") (pin "C") (pinfunction "C_C") (pintype "passive"))
      (node (ref "R125") (pin "1") (pinfunction "1_1") (pintype "passive"))
      (node (ref "R138") (pin "1") (pinfunction "1_1") (pintype "passive"))
      (node (ref "T49") (pin "3") (pinfunction "C_3") (pintype "passive"))
    )
    (net (code "171") (name "Net-(T50-B)") (class "Default")
      (node (ref "R136") (pin "2") (pinfunction "2_2") (pintype "passive"))
      (node (ref "T50") (pin "1") (pinfunction "B_1") (pintype "passive"))
    )
    (net (code "172") (name "Net-(T50-C)") (class "Default")
      (node (ref "LED28") (pin "C") (pinfunction "C_C") (pintype "passive"))
      (node (ref "R129") (pin "1") (pinfunction "1_1") (pintype "passive"))
      (node (ref "R131") (pin "1") (pinfunction "1_1") (pintype "passive"))
      (node (ref "T50") (pin "3") (pinfunction "C_3") (pintype "passive"))
      (node (ref "T51") (pin "3") (pinfunction "C_3") (pintype "passive"))
    )
    (net (code "173") (name "Net-(T51-B)") (class "Default")
      (node (ref "R137") (pin "2") (pinfunction "2_2") (pintype "passive"))
      (node (ref "T51") (pin "1") (pinfunction "B_1") (pintype "passive"))
    )
    (net (code "174") (name "Net-(T52-B)") (class "Default")
      (node (ref "R138") (pin "2") (pinfunction "2_2") (pintype "passive"))
      (node (ref "T52") (pin "1") (pinfunction "B_1") (pintype "passive"))
    )
    (net (code "175") (name "Net-(T52-C)") (class "Default")
      (node (ref "LED29") (pin "C") (pinfunction "C_C") (pintype "passive"))
      (node (ref "R132") (pin "1") (pinfunction "1_1") (pintype "passive"))
      (node (ref "R139") (pin "1") (pinfunction "1_1") (pintype "passive"))
      (node (ref "T52") (pin "3") (pinfunction "C_3") (pintype "passive"))
    )
    (net (code "176") (name "Net-(T52-E)") (class "Default")
      (node (ref "T52") (pin "2") (pinfunction "E_2") (pintype "passive"))
      (node (ref "T54") (pin "3") (pinfunction "C_3") (pintype "passive"))
    )
    (net (code "177") (name "Net-(T53-B)") (class "Default")
      (node (ref "R139") (pin "2") (pinfunction "2_2") (pintype "passive"))
      (node (ref "T53") (pin "1") (pinfunction "B_1") (pintype "passive"))
    )
    (net (code "178") (name "Net-(T53-C)") (class "Default")
      (node (ref "LED30") (pin "C") (pinfunction "C_C") (pintype "passive"))
      (node (ref "R128") (pin "1") (pinfunction "1_1") (pintype "passive"))
      (node (ref "R134") (pin "1") (pinfunction "1_1") (pintype "passive"))
      (node (ref "T53") (pin "3") (pinfunction "C_3") (pintype "passive"))
    )
    (net (code "179") (name "Net-(T54-B)") (class "Default")
      (node (ref "R142") (pin "2") (pinfunction "2_2") (pintype "passive"))
      (node (ref "T54") (pin "1") (pinfunction "B_1") (pintype "passive"))
    )
    (net (code "180") (name "Net-(T55-B)") (class "Default")
      (node (ref "R147") (pin "2") (pinfunction "2_2") (pintype "passive"))
      (node (ref "T55") (pin "1") (pinfunction "B_1") (pintype "passive"))
    )
    (net (code "181") (name "Net-(T56-B)") (class "Default")
      (node (ref "R148") (pin "2") (pinfunction "2_2") (pintype "passive"))
      (node (ref "T56") (pin "1") (pinfunction "B_1") (pintype "passive"))
    )
    (net (code "182") (name "Net-(T56-C)") (class "Default")
      (node (ref "LED32") (pin "C") (pinfunction "C_C") (pintype "passive"))
      (node (ref "R145") (pin "1") (pinfunction "1_1") (pintype "passive"))
      (node (ref "R147") (pin "1") (pinfunction "1_1") (pintype "passive"))
      (node (ref "T56") (pin "3") (pinfunction "C_3") (pintype "passive"))
      (node (ref "T57") (pin "3") (pinfunction "C_3") (pintype "passive"))
      (node (ref "T58") (pin "3") (pinfunction "C_3") (pintype "passive"))
      (node (ref "T59") (pin "3") (pinfunction "C_3") (pintype "passive"))
    )
    (net (code "183") (name "Net-(T57-B)") (class "Default")
      (node (ref "R149") (pin "2") (pinfunction "2_2") (pintype "passive"))
      (node (ref "T57") (pin "1") (pinfunction "B_1") (pintype "passive"))
    )
    (net (code "184") (name "Net-(T58-B)") (class "Default")
      (node (ref "R150") (pin "2") (pinfunction "2_2") (pintype "passive"))
      (node (ref "T58") (pin "1") (pinfunction "B_1") (pintype "passive"))
    )
    (net (code "185") (name "Net-(T59-B)") (class "Default")
      (node (ref "R151") (pin "2") (pinfunction "2_2") (pintype "passive"))
      (node (ref "T59") (pin "1") (pinfunction "B_1") (pintype "passive"))
    )
    (net (code "186") (name "Net-(T60-B)") (class "Default")
      (node (ref "R159") (pin "2") (pinfunction "2_2") (pintype "passive"))
      (node (ref "T60") (pin "1") (pinfunction "B_1") (pintype "passive"))
    )
    (net (code "187") (name "Net-(T60-C)") (class "Default")
      (node (ref "LED33") (pin "C") (pinfunction "C_C") (pintype "passive"))
      (node (ref "R155") (pin "1") (pinfunction "1_1") (pintype "passive"))
      (node (ref "R160") (pin "1") (pinfunction "1_1") (pintype "passive"))
      (node (ref "T60") (pin "3") (pinfunction "C_3") (pintype "passive"))
    )
    (net (code "188") (name "Net-(T60-E)") (class "Default")
      (node (ref "T60") (pin "2") (pinfunction "E_2") (pintype "passive"))
      (node (ref "T62") (pin "3") (pinfunction "C_3") (pintype "passive"))
    )
    (net (code "189") (name "Net-(T61-B)") (class "Default")
      (node (ref "R160") (pin "2") (pinfunction "2_2") (pintype "passive"))
      (node (ref "T61") (pin "1") (pinfunction "B_1") (pintype "passive"))
    )
    (net (code "190") (name "Net-(T61-C)") (class "Default")
      (node (ref "LED34") (pin "C") (pinfunction "C_C") (pintype "passive"))
      (node (ref "R152") (pin "1") (pinfunction "1_1") (pintype "passive"))
      (node (ref "R157") (pin "1") (pinfunction "1_1") (pintype "passive"))
      (node (ref "T61") (pin "3") (pinfunction "C_3") (pintype "passive"))
    )
    (net (code "191") (name "Net-(T62-B)") (class "Default")
      (node (ref "R161") (pin "2") (pinfunction "2_2") (pintype "passive"))
      (node (ref "T62") (pin "1") (pinfunction "B_1") (pintype "passive"))
    )
    (net (code "192") (name "T") (class "Default")
      (node (ref "JP1") (pin "6") (pinfunction "6_6") (pintype "passive"))
      (node (ref "R184") (pin "1") (pinfunction "1_1") (pintype "passive"))
      (node (ref "R184") (pin "2") (pinfunction "2_2") (pintype "passive"))
      (node (ref "R215") (pin "1") (pinfunction "1_1") (pintype "passive"))
      (node (ref "R215") (pin "2") (pinfunction "2_2") (pintype "passive"))
      (node (ref "R216") (pin "1") (pinfunction "1_1") (pintype "passive"))
      (node (ref "R216") (pin "2") (pinfunction "2_2") (pintype "passive"))
      (node (ref "R24") (pin "1") (pinfunction "1_1") (pintype "passive"))
      (node (ref "R33") (pin "1") (pinfunction "1_1") (pintype "passive"))
      (node (ref "R46") (pin "1") (pinfunction "1_1") (pintype "passive"))
      (node (ref "R56") (pin "1") (pinfunction "1_1") (pintype "passive"))
      (node (ref "R87") (pin "1") (pinfunction "1_1") (pintype "passive"))
      (node (ref "R9") (pin "1") (pinfunction "1_1") (pintype "passive"))
    )
    (net (code "193") (name "VCC") (class "Default")
      (node (ref "JP1") (pin "2") (pinfunction "2_2") (pintype "passive"))
      (node (ref "R1") (pin "2") (pinfunction "2_2") (pintype "passive"))
      (node (ref "R108") (pin "2") (pinfunction "2_2") (pintype "passive"))
      (node (ref "R109") (pin "2") (pinfunction "2_2") (pintype "passive"))
      (node (ref "R111") (pin "2") (pinfunction "2_2") (pintype "passive"))
      (node (ref "R112") (pin "2") (pinfunction "2_2") (pintype "passive"))
      (node (ref "R113") (pin "2") (pinfunction "2_2") (pintype "passive"))
      (node (ref "R114") (pin "2") (pinfunction "2_2") (pintype "passive"))
      (node (ref "R116") (pin "2") (pinfunction "2_2") (pintype "passive"))
      (node (ref "R117") (pin "2") (pinfunction "2_2") (pintype "passive"))
      (node (ref "R125") (pin "2") (pinfunction "2_2") (pintype "passive"))
      (node (ref "R126") (pin "2") (pinfunction "2_2") (pintype "passive"))
      (node (ref "R129") (pin "2") (pinfunction "2_2") (pintype "passive"))
      (node (ref "R130") (pin "2") (pinfunction "2_2") (pintype "passive"))
      (node (ref "R132") (pin "2") (pinfunction "2_2") (pintype "passive"))
      (node (ref "R133") (pin "2") (pinfunction "2_2") (pintype "passive"))
      (node (ref "R134") (pin "2") (pinfunction "2_2") (pintype "passive"))
      (node (ref "R135") (pin "2") (pinfunction "2_2") (pintype "passive"))
      (node (ref "R143") (pin "2") (pinfunction "2_2") (pintype "passive"))
      (node (ref "R144") (pin "2") (pinfunction "2_2") (pintype "passive"))
      (node (ref "R145") (pin "2") (pinfunction "2_2") (pintype "passive"))
      (node (ref "R146") (pin "2") (pinfunction "2_2") (pintype "passive"))
      (node (ref "R15") (pin "2") (pinfunction "2_2") (pintype "passive"))
      (node (ref "R155") (pin "2") (pinfunction "2_2") (pintype "passive"))
      (node (ref "R156") (pin "2") (pinfunction "2_2") (pintype "passive"))
      (node (ref "R157") (pin "2") (pinfunction "2_2") (pintype "passive"))
      (node (ref "R158") (pin "2") (pinfunction "2_2") (pintype "passive"))
      (node (ref "R16") (pin "2") (pinfunction "2_2") (pintype "passive"))
      (node (ref "R164") (pin "1") (pinfunction "1_1") (pintype "passive"))
      (node (ref "R165") (pin "2") (pinfunction "2_2") (pintype "passive"))
      (node (ref "R17") (pin "2") (pinfunction "2_2") (pintype "passive"))
      (node (ref "R171") (pin "1") (pinfunction "1_1") (pintype "passive"))
      (node (ref "R172") (pin "2") (pinfunction "2_2") (pintype "passive"))
      (node (ref "R173") (pin "1") (pinfunction "1_1") (pintype "passive"))
      (node (ref "R174") (pin "2") (pinfunction "2_2") (pintype "passive"))
      (node (ref "R175") (pin "1") (pinfunction "1_1") (pintype "passive"))
      (node (ref "R176") (pin "2") (pinfunction "2_2") (pintype "passive"))
      (node (ref "R178") (pin "1") (pinfunction "1_1") (pintype "passive"))
      (node (ref "R179") (pin "2") (pinfunction "2_2") (pintype "passive"))
      (node (ref "R18") (pin "2") (pinfunction "2_2") (pintype "passive"))
      (node (ref "R180") (pin "1") (pinfunction "1_1") (pintype "passive"))
      (node (ref "R180") (pin "2") (pinfunction "2_2") (pintype "passive"))
      (node (ref "R182") (pin "2") (pinfunction "2_2") (pintype "passive"))
      (node (ref "R183") (pin "1") (pinfunction "1_1") (pintype "passive"))
      (node (ref "R185") (pin "1") (pinfunction "1_1") (pintype "passive"))
      (node (ref "R186") (pin "2") (pinfunction "2_2") (pintype "passive"))
      (node (ref "R187") (pin "1") (pinfunction "1_1") (pintype "passive"))
      (node (ref "R187") (pin "2") (pinfunction "2_2") (pintype "passive"))
      (node (ref "R194") (pin "1") (pinfunction "1_1") (pintype "passive"))
      (node (ref "R195") (pin "2") (pinfunction "2_2") (pintype "passive"))
      (node (ref "R196") (pin "1") (pinfunction "1_1") (pintype "passive"))
      (node (ref "R197") (pin "2") (pinfunction "2_2") (pintype "passive"))
      (node (ref "R198") (pin "1") (pinfunction "1_1") (pintype "passive"))
      (node (ref "R199") (pin "2") (pinfunction "2_2") (pintype "passive"))
      (node (ref "R2") (pin "2") (pinfunction "2_2") (pintype "passive"))
      (node (ref "R238") (pin "1") (pinfunction "1_1") (pintype "passive"))
      (node (ref "R239") (pin "2") (pinfunction "2_2") (pintype "passive"))
      (node (ref "R240") (pin "1") (pinfunction "1_1") (pintype "passive"))
      (node (ref "R240") (pin "2") (pinfunction "2_2") (pintype "passive"))
      (node (ref "R241") (pin "1") (pinfunction "1_1") (pintype "passive"))
      (node (ref "R242") (pin "2") (pinfunction "2_2") (pintype "passive"))
      (node (ref "R243") (pin "1") (pinfunction "1_1") (pintype "passive"))
      (node (ref "R243") (pin "2") (pinfunction "2_2") (pintype "passive"))
      (node (ref "R244") (pin "1") (pinfunction "1_1") (pintype "passive"))
      (node (ref "R245") (pin "2") (pinfunction "2_2") (pintype "passive"))
      (node (ref "R246") (pin "1") (pinfunction "1_1") (pintype "passive"))
      (node (ref "R246") (pin "2") (pinfunction "2_2") (pintype "passive"))
      (node (ref "R247") (pin "1") (pinfunction "1_1") (pintype "passive"))
      (node (ref "R247") (pin "2") (pinfunction "2_2") (pintype "passive"))
      (node (ref "R25") (pin "2") (pinfunction "2_2") (pintype "passive"))
      (node (ref "R26") (pin "2") (pinfunction "2_2") (pintype "passive"))
      (node (ref "R29") (pin "2") (pinfunction "2_2") (pintype "passive"))
      (node (ref "R30") (pin "2") (pinfunction "2_2") (pintype "passive"))
      (node (ref "R31") (pin "2") (pinfunction "2_2") (pintype "passive"))
      (node (ref "R32") (pin "2") (pinfunction "2_2") (pintype "passive"))
      (node (ref "R38") (pin "2") (pinfunction "2_2") (pintype "passive"))
      (node (ref "R39") (pin "2") (pinfunction "2_2") (pintype "passive"))
      (node (ref "R40") (pin "2") (pinfunction "2_2") (pintype "passive"))
      (node (ref "R41") (pin "2") (pinfunction "2_2") (pintype "passive"))
      (node (ref "R47") (pin "2") (pinfunction "2_2") (pintype "passive"))
      (node (ref "R48") (pin "2") (pinfunction "2_2") (pintype "passive"))
      (node (ref "R49") (pin "2") (pinfunction "2_2") (pintype "passive"))
      (node (ref "R5") (pin "2") (pinfunction "2_2") (pintype "passive"))
      (node (ref "R50") (pin "2") (pinfunction "2_2") (pintype "passive"))
      (node (ref "R6") (pin "2") (pinfunction "2_2") (pintype "passive"))
      (node (ref "R60") (pin "2") (pinfunction "2_2") (pintype "passive"))
      (node (ref "R61") (pin "2") (pinfunction "2_2") (pintype "passive"))
      (node (ref "R63") (pin "2") (pinfunction "2_2") (pintype "passive"))
      (node (ref "R64") (pin "2") (pinfunction "2_2") (pintype "passive"))
      (node (ref "R68") (pin "2") (pinfunction "2_2") (pintype "passive"))
      (node (ref "R69") (pin "2") (pinfunction "2_2") (pintype "passive"))
      (node (ref "R7") (pin "2") (pinfunction "2_2") (pintype "passive"))
      (node (ref "R71") (pin "2") (pinfunction "2_2") (pintype "passive"))
      (node (ref "R72") (pin "2") (pinfunction "2_2") (pintype "passive"))
      (node (ref "R74") (pin "2") (pinfunction "2_2") (pintype "passive"))
      (node (ref "R75") (pin "2") (pinfunction "2_2") (pintype "passive"))
      (node (ref "R76") (pin "2") (pinfunction "2_2") (pintype "passive"))
      (node (ref "R77") (pin "2") (pinfunction "2_2") (pintype "passive"))
      (node (ref "R8") (pin "2") (pinfunction "2_2") (pintype "passive"))
      (node (ref "R89") (pin "2") (pinfunction "2_2") (pintype "passive"))
      (node (ref "R90") (pin "2") (pinfunction "2_2") (pintype "passive"))
      (node (ref "R91") (pin "2") (pinfunction "2_2") (pintype "passive"))
      (node (ref "R92") (pin "2") (pinfunction "2_2") (pintype "passive"))
      (node (ref "R94") (pin "2") (pinfunction "2_2") (pintype "passive"))
      (node (ref "R95") (pin "2") (pinfunction "2_2") (pintype "passive"))
      (node (ref "R96") (pin "2") (pinfunction "2_2") (pintype "passive"))
      (node (ref "R97") (pin "2") (pinfunction "2_2") (pintype "passive"))
    )
    (net (code "194") (name "X") (class "Default")
      (node (ref "JP1") (pin "3") (pinfunction "3_3") (pintype "passive"))
      (node (ref "R127") (pin "1") (pinfunction "1_1") (pintype "passive"))
      (node (ref "R148") (pin "1") (pinfunction "1_1") (pintype "passive"))
      (node (ref "R167") (pin "1") (pinfunction "1_1") (pintype "passive"))
      (node (ref "R168") (pin "2") (pinfunction "2_2") (pintype "passive"))
      (node (ref "R19") (pin "1") (pinfunction "1_1") (pintype "passive"))
      (node (ref "R208") (pin "1") (pinfunction "1_1") (pintype "passive"))
      (node (ref "R208") (pin "2") (pinfunction "2_2") (pintype "passive"))
      (node (ref "R209") (pin "1") (pinfunction "1_1") (pintype "passive"))
      (node (ref "R209") (pin "2") (pinfunction "2_2") (pintype "passive"))
      (node (ref "R210") (pin "1") (pinfunction "1_1") (pintype "passive"))
      (node (ref "R210") (pin "2") (pinfunction "2_2") (pintype "passive"))
      (node (ref "R211") (pin "1") (pinfunction "1_1") (pintype "passive"))
      (node (ref "R211") (pin "2") (pinfunction "2_2") (pintype "passive"))
      (node (ref "R212") (pin "1") (pinfunction "1_1") (pintype "passive"))
      (node (ref "R212") (pin "2") (pinfunction "2_2") (pintype "passive"))
      (node (ref "R217") (pin "1") (pinfunction "1_1") (pintype "passive"))
      (node (ref "R217") (pin "2") (pinfunction "2_2") (pintype "passive"))
      (node (ref "R218") (pin "1") (pinfunction "1_1") (pintype "passive"))
      (node (ref "R218") (pin "2") (pinfunction "2_2") (pintype "passive"))
      (node (ref "R219") (pin "1") (pinfunction "1_1") (pintype "passive"))
      (node (ref "R219") (pin "2") (pinfunction "2_2") (pintype "passive"))
      (node (ref "R220") (pin "1") (pinfunction "1_1") (pintype "passive"))
      (node (ref "R220") (pin "2") (pinfunction "2_2") (pintype "passive"))
      (node (ref "R83") (pin "1") (pinfunction "1_1") (pintype "passive"))
    )
    (net (code "195") (name "Y") (class "Default")
      (node (ref "JP1") (pin "4") (pinfunction "4_4") (pintype "passive"))
      (node (ref "R118") (pin "1") (pinfunction "1_1") (pintype "passive"))
      (node (ref "R136") (pin "1") (pinfunction "1_1") (pintype "passive"))
      (node (ref "R159") (pin "1") (pinfunction "1_1") (pintype "passive"))
      (node (ref "R166") (pin "1") (pinfunction "1_1") (pintype "passive"))
      (node (ref "R166") (pin "2") (pinfunction "2_2") (pintype "passive"))
      (node (ref "R181") (pin "1") (pinfunction "1_1") (pintype "passive"))
      (node (ref "R183") (pin "2") (pinfunction "2_2") (pintype "passive"))
      (node (ref "R201") (pin "1") (pinfunction "1_1") (pintype "passive"))
      (node (ref "R201") (pin "2") (pinfunction "2_2") (pintype "passive"))
      (node (ref "R202") (pin "1") (pinfunction "1_1") (pintype "passive"))
      (node (ref "R202") (pin "2") (pinfunction "2_2") (pintype "passive"))
      (node (ref "R203") (pin "1") (pinfunction "1_1") (pintype "passive"))
      (node (ref "R203") (pin "2") (pinfunction "2_2") (pintype "passive"))
      (node (ref "R204") (pin "1") (pinfunction "1_1") (pintype "passive"))
      (node (ref "R204") (pin "2") (pinfunction "2_2") (pintype "passive"))
      (node (ref "R205") (pin "1") (pinfunction "1_1") (pintype "passive"))
      (node (ref "R205") (pin "2") (pinfunction "2_2") (pintype "passive"))
      (node (ref "R206") (pin "1") (pinfunction "1_1") (pintype "passive"))
      (node (ref "R206") (pin "2") (pinfunction "2_2") (pintype "passive"))
      (node (ref "R207") (pin "1") (pinfunction "1_1") (pintype "passive"))
      (node (ref "R207") (pin "2") (pinfunction "2_2") (pintype "passive"))
      (node (ref "R22") (pin "1") (pinfunction "1_1") (pintype "passive"))
      (node (ref "R3") (pin "1") (pinfunction "1_1") (pintype "passive"))
      (node (ref "R52") (pin "1") (pinfunction "1_1") (pintype "passive"))
      (node (ref "R85") (pin "1") (pinfunction "1_1") (pintype "passive"))
    )
    (net (code "196") (name "Z") (class "Default")
      (node (ref "JP1") (pin "5") (pinfunction "5_5") (pintype "passive"))
      (node (ref "R102") (pin "1") (pinfunction "1_1") (pintype "passive"))
      (node (ref "R169") (pin "1") (pinfunction "1_1") (pintype "passive"))
      (node (ref "R169") (pin "2") (pinfunction "2_2") (pintype "passive"))
      (node (ref "R170") (pin "1") (pinfunction "1_1") (pintype "passive"))
      (node (ref "R170") (pin "2") (pinfunction "2_2") (pintype "passive"))
      (node (ref "R177") (pin "1") (pinfunction "1_1") (pintype "passive"))
      (node (ref "R177") (pin "2") (pinfunction "2_2") (pintype "passive"))
      (node (ref "R191") (pin "1") (pinfunction "1_1") (pintype "passive"))
      (node (ref "R192") (pin "2") (pinfunction "2_2") (pintype "passive"))
      (node (ref "R193") (pin "1") (pinfunction "1_1") (pintype "passive"))
      (node (ref "R193") (pin "2") (pinfunction "2_2") (pintype "passive"))
      (node (ref "R20") (pin "1") (pinfunction "1_1") (pintype "passive"))
      (node (ref "R213") (pin "1") (pinfunction "1_1") (pintype "passive"))
      (node (ref "R213") (pin "2") (pinfunction "2_2") (pintype "passive"))
      (node (ref "R214") (pin "1") (pinfunction "1_1") (pintype "passive"))
      (node (ref "R214") (pin "2") (pinfunction "2_2") (pintype "passive"))
      (node (ref "R27") (pin "1") (pinfunction "1_1") (pintype "passive"))
      (node (ref "R44") (pin "1") (pinfunction "1_1") (pintype "passive"))
      (node (ref "R70") (pin "1") (pinfunction "1_1") (pintype "passive"))
    )
  )
)
